# BSB-LAN-Full.net
KiCad netlist of a schematic drawn in EAGLE
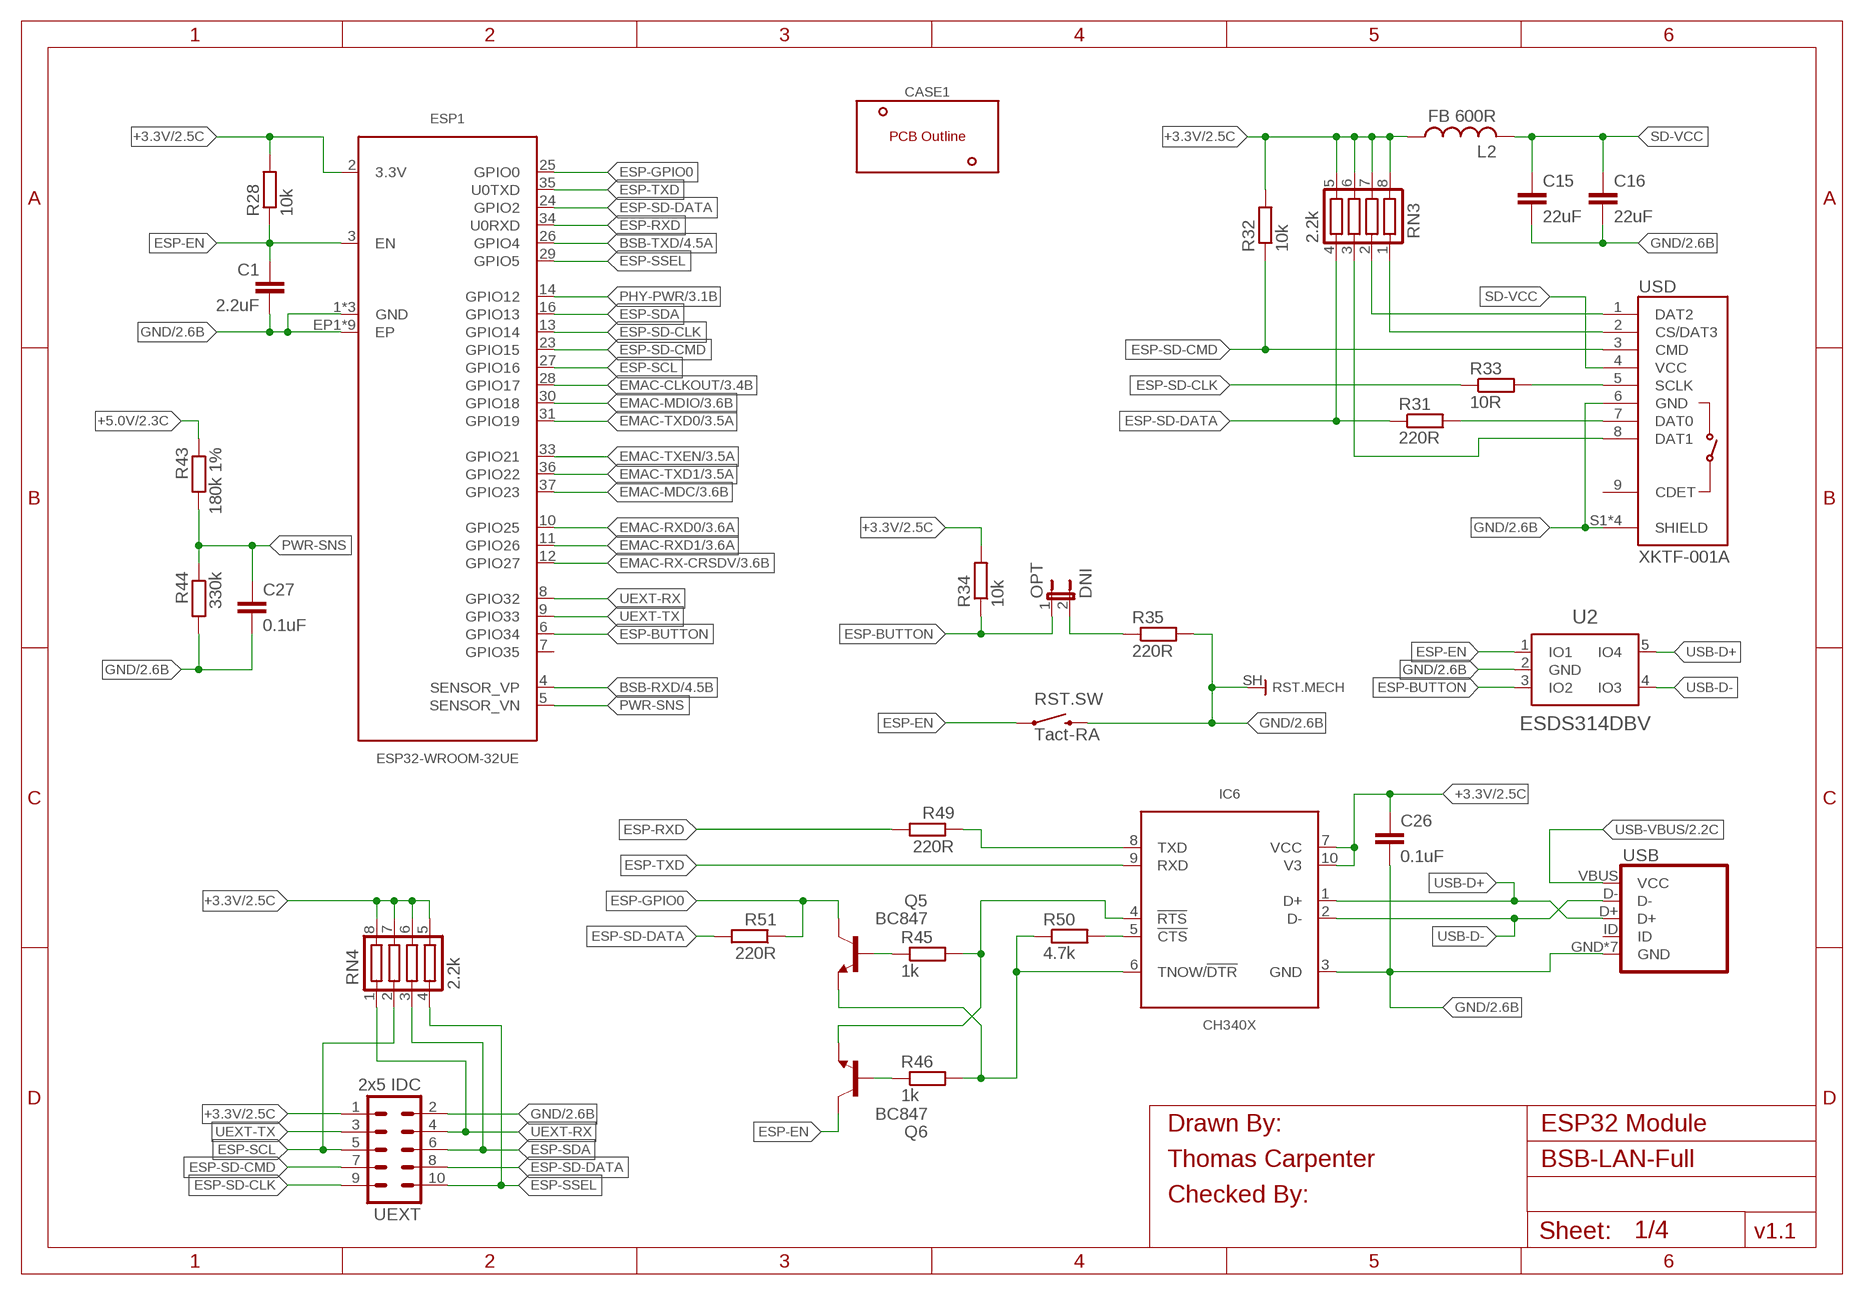
[diagram p0: schematic, sheet 1]
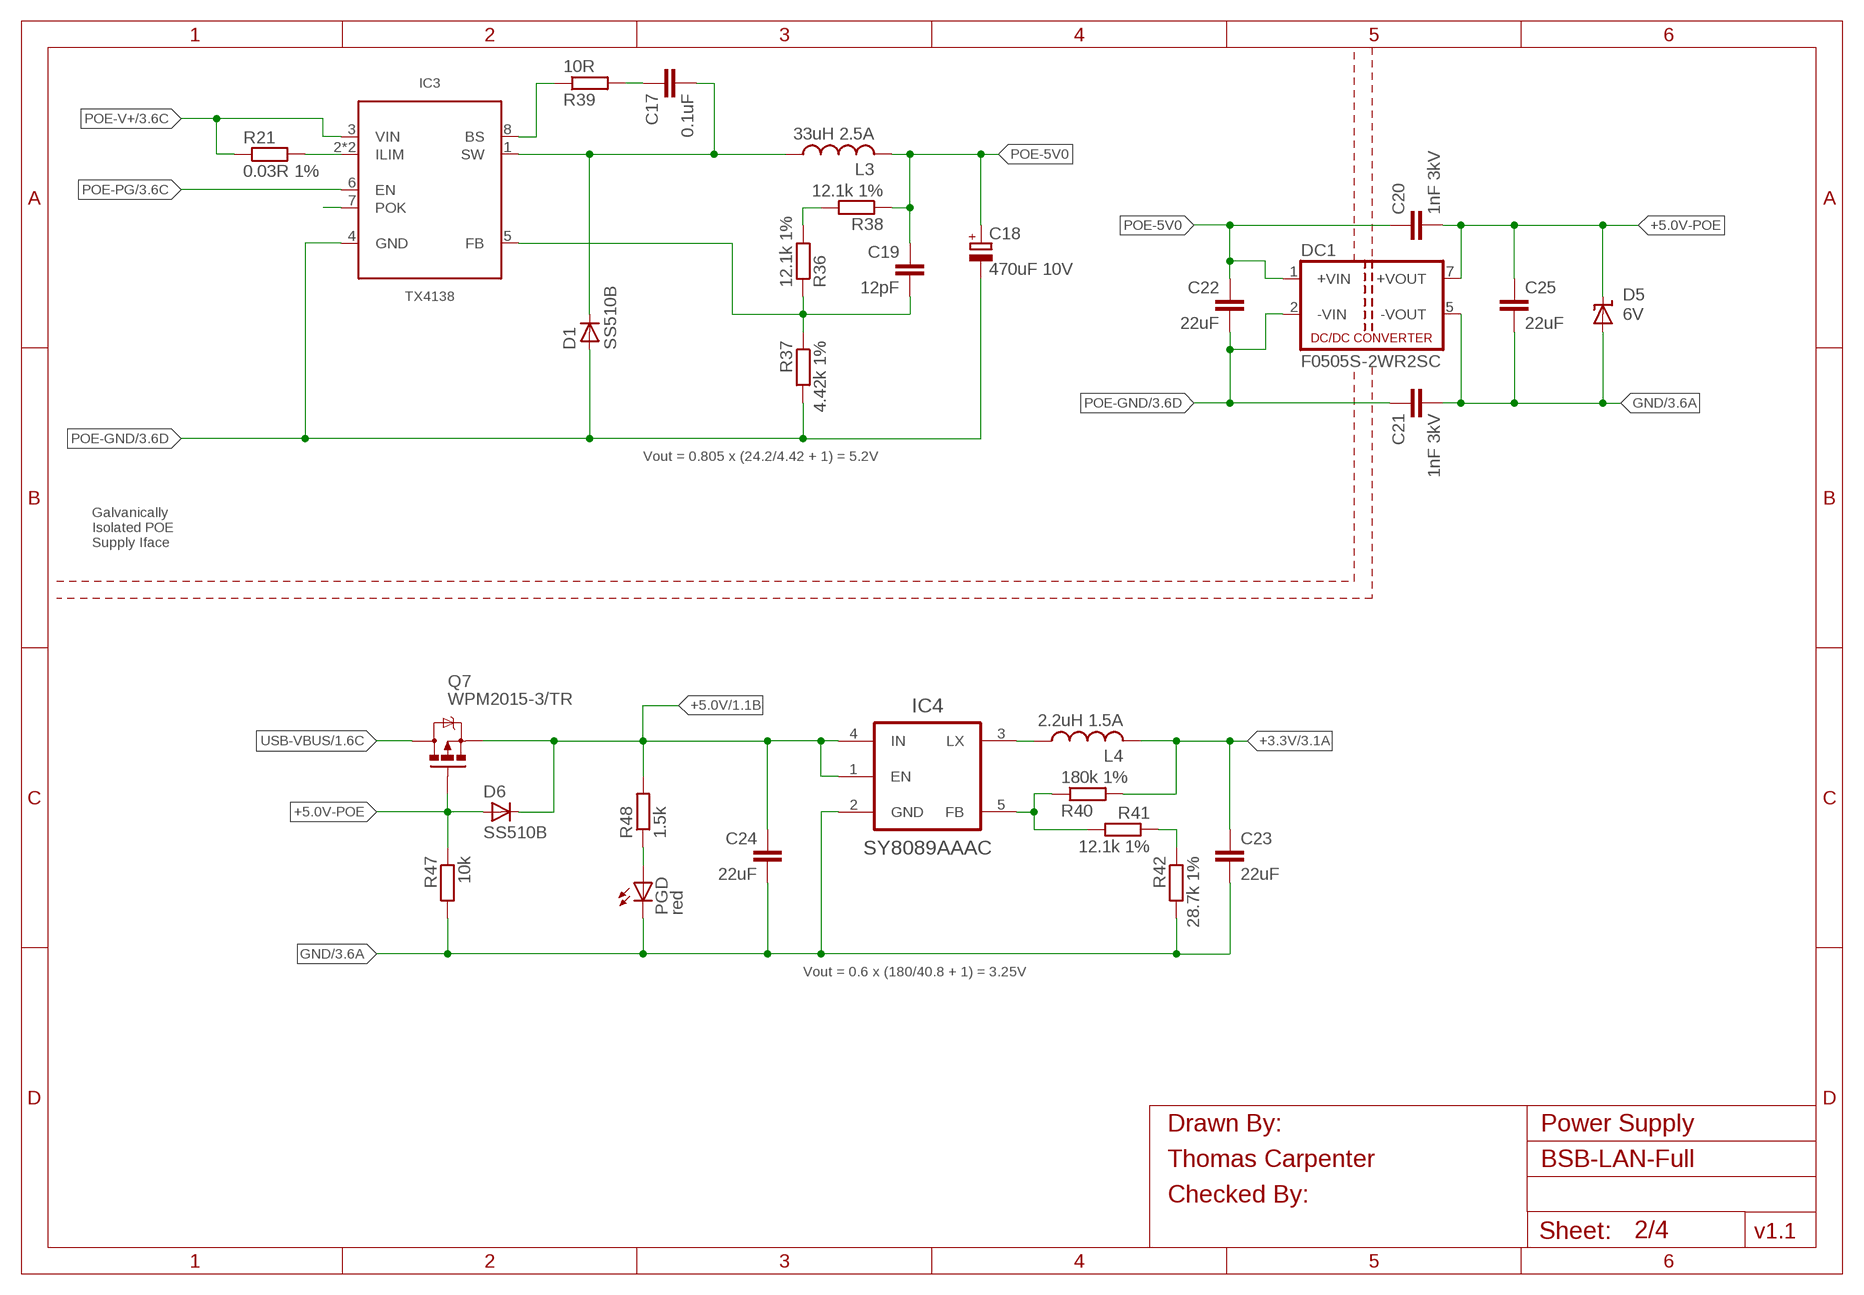
[diagram p1: schematic, sheet 2]
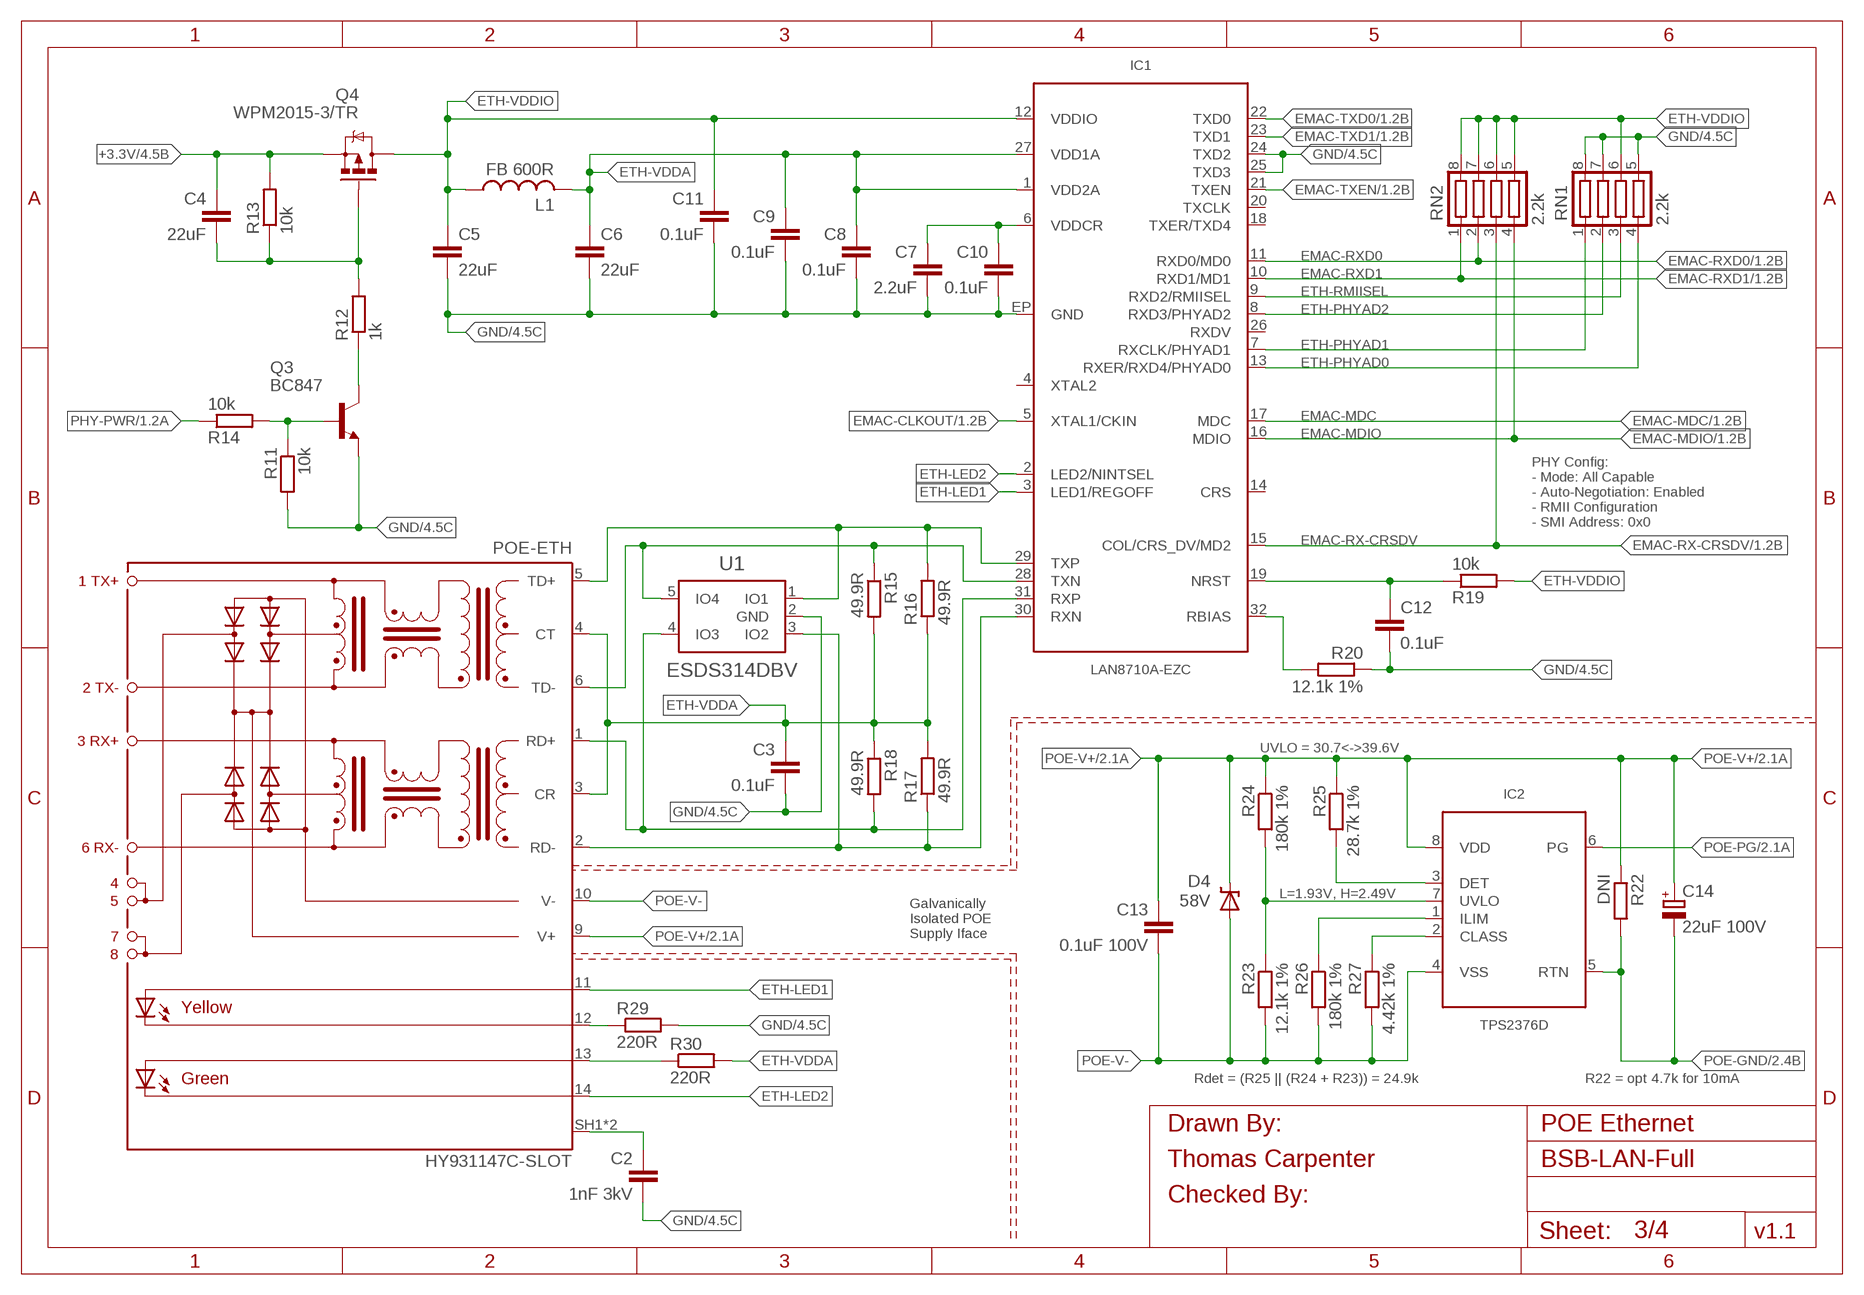
[diagram p2: schematic, sheet 3]
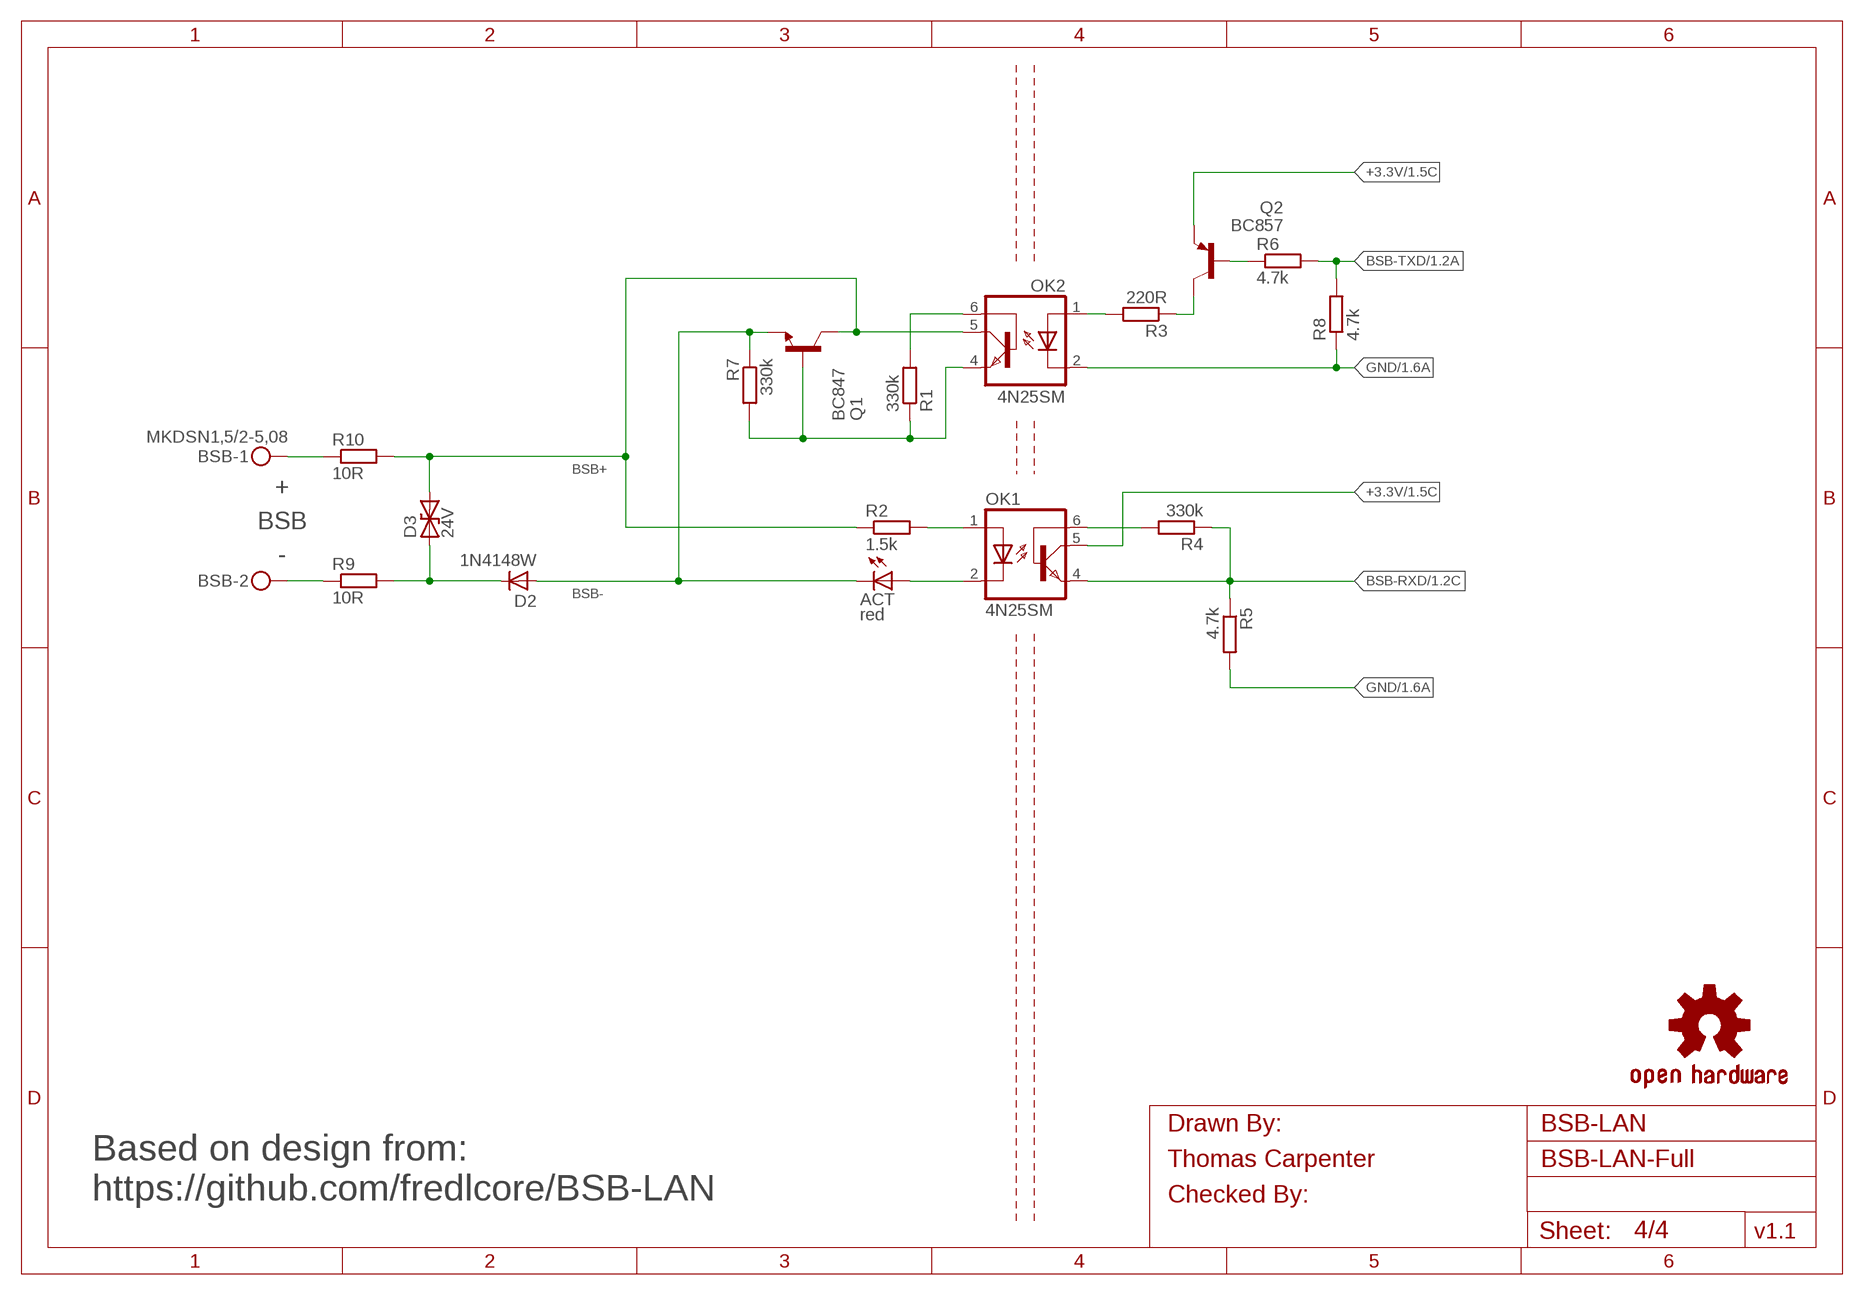
[diagram p3: schematic, sheet 4]

(export (version "E")
  (design (tool "Eeschema 10.0.6"))
  (components
    (comp (ref "ACT")
      (value "red")
      (footprint "eagle-import:CHIP-LED0603")
      (fields (field (name "LCSC_PART") "C2286"))
      (libsource (lib "eagle-import") (part "LEDCHIPLED_0603"))
    )
    (comp (ref "BSB")
      (value "MKDSN1,5/2-5,08")
      (footprint "eagle-import:MKDSN1_5-2-5_08")
      (fields (field (name "LCSC_PART") "C5183989"))
      (libsource (lib "eagle-import") (part "MKDSN1,5/2-5,08"))
    )
    (comp (ref "D2")
      (value "1N4148W")
      (footprint "eagle-import:SOD123")
      (fields (field (name "LCSC_PART") "C81598"))
      (libsource (lib "eagle-import") (part "DIODE-SOD123"))
    )
    (comp (ref "D3")
      (value "24V")
      (footprint "eagle-import:SMBG")
      (fields (field (name "LCSC_PART") "C83268"))
      (libsource (lib "eagle-import") (part "TVS-BIDIRSMB"))
    )
    (comp (ref "OK1")
      (value "4N25SM")
      (footprint "eagle-import:DIL6-SMD")
      (fields (field (name "LCSC_PART") "C258246") (field (name "LCSC_PART_1") "C258246"))
      (libsource (lib "eagle-import") (part "4N?MS25"))
    )
    (comp (ref "OK2")
      (value "4N25SM")
      (footprint "eagle-import:DIL6-SMD")
      (fields (field (name "LCSC_PART") "C258246") (field (name "LCSC_PART_1") "C258246"))
      (libsource (lib "eagle-import") (part "4N?MS25"))
    )
    (comp (ref "Q1")
      (value "BC847")
      (footprint "eagle-import:SOT23")
      (fields (field (name "LCSC_PART") "C130417") (field (name "LCSC_PART_1") "C130417"))
      (libsource (lib "eagle-import") (part "BC847"))
    )
    (comp (ref "Q2")
      (value "BC857")
      (footprint "eagle-import:SOT23-BEC")
      (fields (field (name "LCSC_PART") "C426782") (field (name "LCSC_PART_1") "C426782"))
      (libsource (lib "eagle-import") (part "BC857"))
    )
    (comp (ref "R1")
      (value "330k")
      (footprint "eagle-import:R0603")
      (fields (field (name "LCSC_PART") "C23137"))
      (libsource (lib "eagle-import") (part "R-EU_R0603"))
    )
    (comp (ref "R2")
      (value "1.5k")
      (footprint "eagle-import:R0603")
      (fields (field (name "LCSC_PART") "C22843"))
      (libsource (lib "eagle-import") (part "R-EU_R0603"))
    )
    (comp (ref "R3")
      (value "220R")
      (footprint "eagle-import:R0402")
      (fields (field (name "LCSC_PART") "C25091"))
      (libsource (lib "eagle-import") (part "R-EU_R0402"))
    )
    (comp (ref "R4")
      (value "330k")
      (footprint "eagle-import:R0603")
      (fields (field (name "LCSC_PART") "C23137"))
      (libsource (lib "eagle-import") (part "R-EU_R0603"))
    )
    (comp (ref "R5")
      (value "4.7k")
      (footprint "eagle-import:R0402")
      (fields (field (name "LCSC_PART") "C25900"))
      (libsource (lib "eagle-import") (part "R-EU_R0402"))
    )
    (comp (ref "R6")
      (value "4.7k")
      (footprint "eagle-import:R0402")
      (fields (field (name "LCSC_PART") "C25900"))
      (libsource (lib "eagle-import") (part "R-EU_R0402"))
    )
    (comp (ref "R7")
      (value "330k")
      (footprint "eagle-import:R0603")
      (fields (field (name "LCSC_PART") "C23137"))
      (libsource (lib "eagle-import") (part "R-EU_R0603"))
    )
    (comp (ref "R8")
      (value "4.7k")
      (footprint "eagle-import:R0402")
      (fields (field (name "LCSC_PART") "C25900"))
      (libsource (lib "eagle-import") (part "R-EU_R0402"))
    )
    (comp (ref "R9")
      (value "10R")
      (footprint "eagle-import:R0603")
      (fields (field (name "LCSC_PART") "C22859"))
      (libsource (lib "eagle-import") (part "R-EU_R0603"))
    )
    (comp (ref "R10")
      (value "10R")
      (footprint "eagle-import:R0603")
      (fields (field (name "LCSC_PART") "C22859"))
      (libsource (lib "eagle-import") (part "R-EU_R0603"))
    )
    (comp (ref "U$3")
      (value "DNI")
      (footprint "eagle-import:OSHW-LOGO-M")
      (libsource (lib "eagle-import") (part "OSHW-LOGOM"))
    )
    (comp (ref "C1")
      (value "2.2uF")
      (footprint "eagle-import:C0603")
      (fields (field (name "LCSC_PART") "C23630"))
      (libsource (lib "eagle-import") (part "C-EUC0603"))
    )
    (comp (ref "C15")
      (value "22uF")
      (footprint "eagle-import:C0805L")
      (fields (field (name "LCSC_PART") "C45783"))
      (libsource (lib "eagle-import") (part "C-EUC0805L"))
    )
    (comp (ref "C16")
      (value "22uF")
      (footprint "eagle-import:C0805L")
      (fields (field (name "LCSC_PART") "C45783"))
      (libsource (lib "eagle-import") (part "C-EUC0805L"))
    )
    (comp (ref "C26")
      (value "0.1uF")
      (footprint "eagle-import:C0603L")
      (fields (field (name "LCSC_PART") "C113803"))
      (libsource (lib "eagle-import") (part "C-EUC0603L"))
    )
    (comp (ref "C27")
      (value "0.1uF")
      (footprint "eagle-import:C0603L")
      (fields (field (name "LCSC_PART") "C113803"))
      (libsource (lib "eagle-import") (part "C-EUC0603L"))
    )
    (comp (ref "CASE1")
      (value "DNI")
      (footprint "eagle-import:CNMB_2-")
      (libsource (lib "eagle-import") (part "CNMB/2"))
    )
    (comp (ref "ESP1")
      (value "ESP32-WROOM-32UE")
      (footprint "eagle-import:ESP32-WROOM-32UE")
      (fields (field (name "LCSC_PART") "C701344"))
      (libsource (lib "eagle-import") (part "ESP32-WROOM-32UE"))
    )
    (comp (ref "IC6")
      (value "CH340X")
      (footprint "eagle-import:MSOP10")
      (fields (field (name "LCSC_PART") "C3035748"))
      (libsource (lib "eagle-import") (part "CH340X"))
    )
    (comp (ref "L2")
      (value "FB 600R")
      (footprint "eagle-import:L2010")
      (fields (field (name "LCSC_PART") "C1017"))
      (libsource (lib "eagle-import") (part "L-USL0805"))
    )
    (comp (ref "OPT")
      (value "DNI")
      (footprint "eagle-import:1X02-2MM")
      (libsource (lib "eagle-import") (part "JUMPER-2-2MM"))
    )
    (comp (ref "Q5")
      (value "BC847")
      (footprint "eagle-import:SOT23")
      (fields (field (name "LCSC_PART") "C130417") (field (name "LCSC_PART_1") "C130417"))
      (libsource (lib "eagle-import") (part "BC847"))
    )
    (comp (ref "Q6")
      (value "BC847")
      (footprint "eagle-import:SOT23")
      (fields (field (name "LCSC_PART") "C130417"))
      (libsource (lib "eagle-import") (part "BC847"))
    )
    (comp (ref "R28")
      (value "10k")
      (footprint "eagle-import:R0402")
      (fields (field (name "LCSC_PART") "C25744"))
      (libsource (lib "eagle-import") (part "R-EU_R0402"))
    )
    (comp (ref "R31")
      (value "220R")
      (footprint "eagle-import:R0402")
      (fields (field (name "LCSC_PART") "C25091"))
      (libsource (lib "eagle-import") (part "R-EU_R0402"))
    )
    (comp (ref "R32")
      (value "10k")
      (footprint "eagle-import:R0402")
      (fields (field (name "LCSC_PART") "C25744"))
      (libsource (lib "eagle-import") (part "R-EU_R0402"))
    )
    (comp (ref "R33")
      (value "10R")
      (footprint "eagle-import:R0603L")
      (fields (field (name "LCSC_PART") "C22859"))
      (libsource (lib "eagle-import") (part "R-EU_R0603L"))
    )
    (comp (ref "R34")
      (value "10k")
      (footprint "eagle-import:R0402")
      (fields (field (name "LCSC_PART") "C25744"))
      (libsource (lib "eagle-import") (part "R-EU_R0402"))
    )
    (comp (ref "R35")
      (value "220R")
      (footprint "eagle-import:R0402")
      (fields (field (name "LCSC_PART") "C25091"))
      (libsource (lib "eagle-import") (part "R-EU_R0402"))
    )
    (comp (ref "R43")
      (value "180k 1%")
      (footprint "eagle-import:R0402")
      (fields (field (name "LCSC_PART") "C25760"))
      (libsource (lib "eagle-import") (part "R-EU_R0402"))
    )
    (comp (ref "R44")
      (value "330k")
      (footprint "eagle-import:R0603L")
      (fields (field (name "LCSC_PART") "C23137"))
      (libsource (lib "eagle-import") (part "R-EU_R0603L"))
    )
    (comp (ref "R45")
      (value "1k")
      (footprint "eagle-import:R0402")
      (fields (field (name "LCSC_PART") "C11702"))
      (libsource (lib "eagle-import") (part "R-EU_R0402"))
    )
    (comp (ref "R46")
      (value "1k")
      (footprint "eagle-import:R0402")
      (fields (field (name "LCSC_PART") "C11702"))
      (libsource (lib "eagle-import") (part "R-EU_R0402"))
    )
    (comp (ref "R49")
      (value "220R")
      (footprint "eagle-import:R0402")
      (fields (field (name "LCSC_PART") "C25091"))
      (libsource (lib "eagle-import") (part "R-EU_R0402"))
    )
    (comp (ref "R50")
      (value "4.7k")
      (footprint "eagle-import:R0402")
      (fields (field (name "LCSC_PART") "C25900"))
      (libsource (lib "eagle-import") (part "R-EU_R0402"))
    )
    (comp (ref "R51")
      (value "220R")
      (footprint "eagle-import:R0402")
      (fields (field (name "LCSC_PART") "C25091"))
      (libsource (lib "eagle-import") (part "R-EU_R0402"))
    )
    (comp (ref "RN3")
      (value "2.2k")
      (footprint "eagle-import:CTS742C083")
      (fields (field (name "LCSC_PART") "C414564"))
      (libsource (lib "eagle-import") (part "R-NET-04-R1206"))
    )
    (comp (ref "RN4")
      (value "2.2k")
      (footprint "eagle-import:CTS742C083")
      (fields (field (name "LCSC_PART") "C414564"))
      (libsource (lib "eagle-import") (part "R-NET-04-R1206"))
    )
    (comp (ref "RST")
      (value "Tact-RA")
      (footprint "eagle-import:TACTILE_SWITCH_SMD_SIDE_SHL")
      (fields (field (name "LCSC_PART") "C495926"))
      (libsource (lib "eagle-import") (part "SWITCH-MOMENTARY-SHELL-SMD-RA"))
    )
    (comp (ref "U2")
      (value "ESDS314DBV")
      (footprint "eagle-import:DBV0005A-SOT23")
      (fields (field (name "LCSC_PART") "C1847859"))
      (libsource (lib "eagle-import") (part "ESDS314DBV"))
    )
    (comp (ref "UEXT")
      (value "2x5 IDC")
      (footprint "eagle-import:ML10")
      (fields (field (name "LCSC_PART") "C5665"))
      (libsource (lib "eagle-import") (part "ML10"))
    )
    (comp (ref "USB")
      (value "ZX62-B-5PA(33)")
      (footprint "eagle-import:USB-MICROB")
      (fields (field (name "LCSC_PART") "C132561"))
      (libsource (lib "eagle-import") (part "USB_MICROB_PLUG"))
    )
    (comp (ref "USD")
      (value "XKTF-001A")
      (footprint "eagle-import:MICRO-SD")
      (fields (field (name "LCSC_PART") "C381079"))
      (libsource (lib "eagle-import") (part "MICROSD"))
    )
    (comp (ref "C2")
      (value "1nF 3kV")
      (footprint "eagle-import:C1808")
      (fields (field (name "LCSC_PART") "C577300"))
      (libsource (lib "eagle-import") (part "C-EUC1808"))
    )
    (comp (ref "C3")
      (value "0.1uF")
      (footprint "eagle-import:C0603")
      (fields (field (name "LCSC_PART") "C113803"))
      (libsource (lib "eagle-import") (part "C-EUC0603"))
    )
    (comp (ref "C4")
      (value "22uF")
      (footprint "eagle-import:C0805L")
      (fields (field (name "LCSC_PART") "C45783"))
      (libsource (lib "eagle-import") (part "C-EUC0805L"))
    )
    (comp (ref "C5")
      (value "22uF")
      (footprint "eagle-import:C0805L")
      (fields (field (name "LCSC_PART") "C45783"))
      (libsource (lib "eagle-import") (part "C-EUC0805L"))
    )
    (comp (ref "C6")
      (value "22uF")
      (footprint "eagle-import:C0805L")
      (fields (field (name "LCSC_PART") "C45783"))
      (libsource (lib "eagle-import") (part "C-EUC0805L"))
    )
    (comp (ref "C7")
      (value "2.2uF")
      (footprint "eagle-import:C0603")
      (fields (field (name "LCSC_PART") "C23630"))
      (libsource (lib "eagle-import") (part "C-EUC0603"))
    )
    (comp (ref "C8")
      (value "0.1uF")
      (footprint "eagle-import:C0603L")
      (fields (field (name "LCSC_PART") "C113803"))
      (libsource (lib "eagle-import") (part "C-EUC0603L"))
    )
    (comp (ref "C9")
      (value "0.1uF")
      (footprint "eagle-import:C0603L")
      (fields (field (name "LCSC_PART") "C113803"))
      (libsource (lib "eagle-import") (part "C-EUC0603L"))
    )
    (comp (ref "C10")
      (value "0.1uF")
      (footprint "eagle-import:C0603L")
      (fields (field (name "LCSC_PART") "C113803"))
      (libsource (lib "eagle-import") (part "C-EUC0603L"))
    )
    (comp (ref "C11")
      (value "0.1uF")
      (footprint "eagle-import:C0603L")
      (fields (field (name "LCSC_PART") "C113803"))
      (libsource (lib "eagle-import") (part "C-EUC0603L"))
    )
    (comp (ref "C12")
      (value "0.1uF")
      (footprint "eagle-import:C0603L")
      (fields (field (name "LCSC_PART") "C113803"))
      (libsource (lib "eagle-import") (part "C-EUC0603L"))
    )
    (comp (ref "C13")
      (value "0.1uF 100V")
      (footprint "eagle-import:C0603")
      (fields (field (name "LCSC_PART") "C113803"))
      (libsource (lib "eagle-import") (part "C-EUC0603"))
    )
    (comp (ref "C14")
      (value "22uF 100V")
      (footprint "eagle-import:PANASONIC_D")
      (fields (field (name "LCSC_PART") "C487431"))
      (libsource (lib "eagle-import") (part "CPOL-EUD"))
    )
    (comp (ref "D4")
      (value "58V")
      (footprint "eagle-import:SMA")
      (fields (field (name "LCSC_PART") "C151246"))
      (libsource (lib "eagle-import") (part "TVS-UNISMA"))
    )
    (comp (ref "IC1")
      (value "LAN8710A-EZC")
      (footprint "eagle-import:QFN-5X5-32")
      (fields (field (name "LCSC_PART") "C46185"))
      (libsource (lib "eagle-import") (part "LAN8710A-EZC"))
    )
    (comp (ref "IC2")
      (value "TPS2376D")
      (footprint "eagle-import:SOIC8")
      (fields (field (name "LCSC_PART") "C2859892"))
      (libsource (lib "eagle-import") (part "TPS237D6"))
    )
    (comp (ref "L1")
      (value "FB 600R")
      (footprint "eagle-import:L2010")
      (fields (field (name "LCSC_PART") "C1017"))
      (libsource (lib "eagle-import") (part "L-USL0805"))
    )
    (comp (ref "POE-ETH")
      (value "HY931147C-SLOT")
      (footprint "eagle-import:HY931147C-SLOT")
      (fields (field (name "LCSC_PART") "C91754"))
      (libsource (lib "eagle-import") (part "HY931147C-SLOT"))
    )
    (comp (ref "Q3")
      (value "BC847")
      (footprint "eagle-import:SOT23")
      (fields (field (name "LCSC_PART") "C130417"))
      (libsource (lib "eagle-import") (part "BC847"))
    )
    (comp (ref "Q4")
      (value "WPM2015-3/TR")
      (footprint "eagle-import:SOT23")
      (fields (field (name "LCSC_PART") "C7472861"))
      (libsource (lib "eagle-import") (part "WPM2015-3/TR"))
    )
    (comp (ref "R11")
      (value "10k")
      (footprint "eagle-import:R0402")
      (fields (field (name "LCSC_PART") "C25744"))
      (libsource (lib "eagle-import") (part "R-EU_R0402"))
    )
    (comp (ref "R12")
      (value "1k")
      (footprint "eagle-import:R0402")
      (fields (field (name "LCSC_PART") "C11702"))
      (libsource (lib "eagle-import") (part "R-EU_R0402"))
    )
    (comp (ref "R13")
      (value "10k")
      (footprint "eagle-import:R0402")
      (fields (field (name "LCSC_PART") "C25744"))
      (libsource (lib "eagle-import") (part "R-EU_R0402"))
    )
    (comp (ref "R14")
      (value "10k")
      (footprint "eagle-import:R0402")
      (fields (field (name "LCSC_PART") "C25744"))
      (libsource (lib "eagle-import") (part "R-EU_R0402"))
    )
    (comp (ref "R15")
      (value "49.9R")
      (footprint "eagle-import:R0402L")
      (fields (field (name "LCSC_PART") "C25120"))
      (libsource (lib "eagle-import") (part "R-EU_R0402L"))
    )
    (comp (ref "R16")
      (value "49.9R")
      (footprint "eagle-import:R0402L")
      (fields (field (name "LCSC_PART") "C25120"))
      (libsource (lib "eagle-import") (part "R-EU_R0402L"))
    )
    (comp (ref "R17")
      (value "49.9R")
      (footprint "eagle-import:R0402L")
      (fields (field (name "LCSC_PART") "C25120"))
      (libsource (lib "eagle-import") (part "R-EU_R0402L"))
    )
    (comp (ref "R18")
      (value "49.9R")
      (footprint "eagle-import:R0402L")
      (fields (field (name "LCSC_PART") "C25120"))
      (libsource (lib "eagle-import") (part "R-EU_R0402L"))
    )
    (comp (ref "R19")
      (value "10k")
      (footprint "eagle-import:R0402")
      (fields (field (name "LCSC_PART") "C25744"))
      (libsource (lib "eagle-import") (part "R-EU_R0402"))
    )
    (comp (ref "R20")
      (value "12.1k 1%")
      (footprint "eagle-import:R0402")
      (fields (field (name "LCSC_PART") "C25852"))
      (libsource (lib "eagle-import") (part "R-EU_R0402"))
    )
    (comp (ref "R22")
      (value "DNI")
      (footprint "eagle-import:R1206")
      (libsource (lib "eagle-import") (part "R-EU_R1206"))
    )
    (comp (ref "R23")
      (value "12.1k 1%")
      (footprint "eagle-import:R0402")
      (fields (field (name "LCSC_PART") "C25852"))
      (libsource (lib "eagle-import") (part "R-EU_R0402"))
    )
    (comp (ref "R24")
      (value "180k 1%")
      (footprint "eagle-import:R0402")
      (fields (field (name "LCSC_PART") "C25760"))
      (libsource (lib "eagle-import") (part "R-EU_R0402"))
    )
    (comp (ref "R25")
      (value "28.7k 1%")
      (footprint "eagle-import:R0402")
      (fields (field (name "LCSC_PART") "C26972"))
      (libsource (lib "eagle-import") (part "R-EU_R0402"))
    )
    (comp (ref "R26")
      (value "180k 1%")
      (footprint "eagle-import:R0402")
      (fields (field (name "LCSC_PART") "C25760"))
      (libsource (lib "eagle-import") (part "R-EU_R0402"))
    )
    (comp (ref "R27")
      (value "4.42k 1%")
      (footprint "eagle-import:R0402")
      (fields (field (name "LCSC_PART") "C52269"))
      (libsource (lib "eagle-import") (part "R-EU_R0402"))
    )
    (comp (ref "R29")
      (value "220R")
      (footprint "eagle-import:R0402")
      (fields (field (name "LCSC_PART") "C25091"))
      (libsource (lib "eagle-import") (part "R-EU_R0402"))
    )
    (comp (ref "R30")
      (value "220R")
      (footprint "eagle-import:R0402")
      (fields (field (name "LCSC_PART") "C25091"))
      (libsource (lib "eagle-import") (part "R-EU_R0402"))
    )
    (comp (ref "RN1")
      (value "2.2k")
      (footprint "eagle-import:CTS742C083")
      (fields (field (name "LCSC_PART") "C414564"))
      (libsource (lib "eagle-import") (part "R-NET-04-R1206"))
    )
    (comp (ref "RN2")
      (value "2.2k")
      (footprint "eagle-import:CTS742C083")
      (fields (field (name "LCSC_PART") "C414564"))
      (libsource (lib "eagle-import") (part "R-NET-04-R1206"))
    )
    (comp (ref "U1")
      (value "ESDS314DBV")
      (footprint "eagle-import:DBV0005A-SOT23")
      (fields (field (name "LCSC_PART") "C1847859"))
      (libsource (lib "eagle-import") (part "ESDS314DBV"))
    )
    (comp (ref "C17")
      (value "0.1uF")
      (footprint "eagle-import:C0603L")
      (fields (field (name "LCSC_PART") "C113803"))
      (libsource (lib "eagle-import") (part "C-EUC0603L"))
    )
    (comp (ref "C18")
      (value "470uF 10V")
      (footprint "eagle-import:SMC_D")
      (fields (field (name "LCSC_PART") "C4944894"))
      (libsource (lib "eagle-import") (part "CPOL-EUSMCD"))
    )
    (comp (ref "C19")
      (value "12pF")
      (footprint "eagle-import:C0402")
      (fields (field (name "LCSC_PART") "C1547"))
      (libsource (lib "eagle-import") (part "C-EUC0402"))
    )
    (comp (ref "C20")
      (value "1nF 3kV")
      (footprint "eagle-import:C1808")
      (fields (field (name "LCSC_PART") "C577300"))
      (libsource (lib "eagle-import") (part "C-EUC1808"))
    )
    (comp (ref "C21")
      (value "1nF 3kV")
      (footprint "eagle-import:C1808")
      (fields (field (name "LCSC_PART") "C577300"))
      (libsource (lib "eagle-import") (part "C-EUC1808"))
    )
    (comp (ref "C22")
      (value "22uF")
      (footprint "eagle-import:C0805")
      (fields (field (name "LCSC_PART") "C45783"))
      (libsource (lib "eagle-import") (part "C-EUC0805"))
    )
    (comp (ref "C23")
      (value "22uF")
      (footprint "eagle-import:C0805")
      (fields (field (name "LCSC_PART") "C45783"))
      (libsource (lib "eagle-import") (part "C-EUC0805"))
    )
    (comp (ref "C24")
      (value "22uF")
      (footprint "eagle-import:C0805")
      (fields (field (name "LCSC_PART") "C45783"))
      (libsource (lib "eagle-import") (part "C-EUC0805"))
    )
    (comp (ref "C25")
      (value "22uF")
      (footprint "eagle-import:C0805")
      (fields (field (name "LCSC_PART") "C45783"))
      (libsource (lib "eagle-import") (part "C-EUC0805"))
    )
    (comp (ref "D1")
      (value "SS510B")
      (footprint "eagle-import:SMB")
      (fields (field (name "LCSC_PART") "C65011"))
      (libsource (lib "eagle-import") (part "DIODE-SMB"))
    )
    (comp (ref "D5")
      (value "6V")
      (footprint "eagle-import:SMA")
      (fields (field (name "LCSC_PART") "C223993"))
      (libsource (lib "eagle-import") (part "TVS-UNISMA"))
    )
    (comp (ref "D6")
      (value "SS510B")
      (footprint "eagle-import:SMB")
      (fields (field (name "LCSC_PART") "C65011"))
      (libsource (lib "eagle-import") (part "DIODE-SMB"))
    )
    (comp (ref "DC1")
      (value "F0505S-2WR2SC")
      (footprint "eagle-import:SIP7-N")
      (fields (field (name "LCSC_PART") "C909777"))
      (libsource (lib "eagle-import") (part "FS-2WR2SC0505"))
    )
    (comp (ref "IC3")
      (value "TX4138")
      (footprint "eagle-import:SOIC8-EP")
      (fields (field (name "LCSC_PART") "C329267"))
      (libsource (lib "eagle-import") (part "TX4138"))
    )
    (comp (ref "IC4")
      (value "SY8089AAAC")
      (footprint "eagle-import:DBV0005A-SOT23")
      (fields (field (name "LCSC_PART") "C78988"))
      (libsource (lib "eagle-import") (part "SY8089?CAAA"))
    )
    (comp (ref "L3")
      (value "33uH 2.5A")
      (footprint "eagle-import:L6560P")
      (fields (field (name "LCSC_PART") "C2839927"))
      (libsource (lib "eagle-import") (part "L-USL6560P"))
    )
    (comp (ref "L4")
      (value "2.2uH 1.5A")
      (footprint "eagle-import:L4040P")
      (fields (field (name "LCSC_PART") "C135262"))
      (libsource (lib "eagle-import") (part "L-USL4040P"))
    )
    (comp (ref "PGD")
      (value "red")
      (footprint "eagle-import:CHIP-LED0603")
      (fields (field (name "LCSC_PART") "C2286"))
      (libsource (lib "eagle-import") (part "LEDCHIPLED_0603"))
    )
    (comp (ref "Q7")
      (value "WPM2015-3/TR")
      (footprint "eagle-import:SOT23")
      (fields (field (name "LCSC_PART") "C7472861"))
      (libsource (lib "eagle-import") (part "WPM2015-3/TR"))
    )
    (comp (ref "R21")
      (value "0.03R 1%")
      (footprint "eagle-import:R1206")
      (fields (field (name "LCSC_PART") "C163046"))
      (libsource (lib "eagle-import") (part "R-EU_R1206"))
    )
    (comp (ref "R36")
      (value "12.1k 1%")
      (footprint "eagle-import:R0402")
      (fields (field (name "LCSC_PART") "C25852"))
      (libsource (lib "eagle-import") (part "R-EU_R0402"))
    )
    (comp (ref "R37")
      (value "4.42k 1%")
      (footprint "eagle-import:R0402")
      (fields (field (name "LCSC_PART") "C52269"))
      (libsource (lib "eagle-import") (part "R-EU_R0402"))
    )
    (comp (ref "R38")
      (value "12.1k 1%")
      (footprint "eagle-import:R0402")
      (fields (field (name "LCSC_PART") "C25852"))
      (libsource (lib "eagle-import") (part "R-EU_R0402"))
    )
    (comp (ref "R39")
      (value "10R")
      (footprint "eagle-import:R0603L")
      (fields (field (name "LCSC_PART") "C22859"))
      (libsource (lib "eagle-import") (part "R-EU_R0603L"))
    )
    (comp (ref "R40")
      (value "180k 1%")
      (footprint "eagle-import:R0402")
      (fields (field (name "LCSC_PART") "C25760"))
      (libsource (lib "eagle-import") (part "R-EU_R0402"))
    )
    (comp (ref "R41")
      (value "12.1k 1%")
      (footprint "eagle-import:R0402")
      (fields (field (name "LCSC_PART") "C25852"))
      (libsource (lib "eagle-import") (part "R-EU_R0402"))
    )
    (comp (ref "R42")
      (value "28.7k 1%")
      (footprint "eagle-import:R0402")
      (fields (field (name "LCSC_PART") "C26972"))
      (libsource (lib "eagle-import") (part "R-EU_R0402"))
    )
    (comp (ref "R47")
      (value "10k")
      (footprint "eagle-import:R0402")
      (fields (field (name "LCSC_PART") "C25744"))
      (libsource (lib "eagle-import") (part "R-EU_R0402"))
    )
    (comp (ref "R48")
      (value "1.5k")
      (footprint "eagle-import:R0603")
      (fields (field (name "LCSC_PART") "C22843"))
      (libsource (lib "eagle-import") (part "R-EU_R0603"))
    )
  )
  (nets
    (net (code "1") (name "+3.3V") (class "Default")
      (node (ref "C23") (pin "1") (pinfunction "1_1") (pintype "passive"))
      (node (ref "C26") (pin "1") (pinfunction "1_1") (pintype "passive"))
      (node (ref "C4") (pin "1") (pinfunction "1_1") (pintype "passive"))
      (node (ref "ESP1") (pin "2") (pinfunction "3.3V_2") (pintype "power_in"))
      (node (ref "IC6") (pin "10") (pinfunction "V3_10") (pintype "power_in"))
      (node (ref "IC6") (pin "7") (pinfunction "VCC_7") (pintype "power_in"))
      (node (ref "L2") (pin "1") (pinfunction "1_1") (pintype "passive"))
      (node (ref "L4") (pin "2") (pinfunction "2_2") (pintype "passive"))
      (node (ref "OK1") (pin "5") (pinfunction "COL_5") (pintype "passive"))
      (node (ref "Q2") (pin "E") (pinfunction "E_E") (pintype "passive"))
      (node (ref "Q4") (pin "2") (pinfunction "S_2") (pintype "passive"))
      (node (ref "R13") (pin "2") (pinfunction "2_2") (pintype "passive"))
      (node (ref "R28") (pin "2") (pinfunction "2_2") (pintype "passive"))
      (node (ref "R32") (pin "2") (pinfunction "2_2") (pintype "passive"))
      (node (ref "R34") (pin "2") (pinfunction "2_2") (pintype "passive"))
      (node (ref "R40") (pin "2") (pinfunction "2_2") (pintype "passive"))
      (node (ref "RN3") (pin "5") (pinfunction "5_5") (pintype "passive"))
      (node (ref "RN3") (pin "6") (pinfunction "6_6") (pintype "passive"))
      (node (ref "RN3") (pin "7") (pinfunction "7_7") (pintype "passive"))
      (node (ref "RN3") (pin "8") (pinfunction "8_8") (pintype "passive"))
      (node (ref "RN4") (pin "5") (pinfunction "5_5") (pintype "passive"))
      (node (ref "RN4") (pin "6") (pinfunction "6_6") (pintype "passive"))
      (node (ref "RN4") (pin "7") (pinfunction "7_7") (pintype "passive"))
      (node (ref "RN4") (pin "8") (pinfunction "8_8") (pintype "passive"))
      (node (ref "UEXT") (pin "1") (pinfunction "1_1") (pintype "passive"))
    )
    (net (code "2") (name "+5.0V") (class "Default")
      (node (ref "C24") (pin "1") (pinfunction "1_1") (pintype "passive"))
      (node (ref "D6") (pin "C") (pinfunction "C_C") (pintype "passive"))
      (node (ref "IC4") (pin "1") (pinfunction "EN_1") (pintype "input"))
      (node (ref "IC4") (pin "4") (pinfunction "IN_4") (pintype "power_in"))
      (node (ref "Q7") (pin "2") (pinfunction "S_2") (pintype "passive"))
      (node (ref "R43") (pin "1") (pinfunction "1_1") (pintype "passive"))
      (node (ref "R48") (pin "2") (pinfunction "2_2") (pintype "passive"))
    )
    (net (code "3") (name "+5.0V-POE") (class "Default")
      (node (ref "C20") (pin "2") (pinfunction "2_2") (pintype "passive"))
      (node (ref "C25") (pin "1") (pinfunction "1_1") (pintype "passive"))
      (node (ref "D5") (pin "C") (pinfunction "C_C") (pintype "passive"))
      (node (ref "D6") (pin "A") (pinfunction "A_A") (pintype "passive"))
      (node (ref "DC1") (pin "7") (pinfunction "+VOUT_7") (pintype "passive"))
      (node (ref "Q7") (pin "1") (pinfunction "G_1") (pintype "passive"))
      (node (ref "R47") (pin "1") (pinfunction "1_1") (pintype "passive"))
    )
    (net (code "4") (name "BSB+") (class "Default")
      (node (ref "D3") (pin "2") (pinfunction "2_2") (pintype "passive"))
      (node (ref "OK2") (pin "5") (pinfunction "COL_5") (pintype "passive"))
      (node (ref "Q1") (pin "3") (pinfunction "C_3") (pintype "passive"))
      (node (ref "R10") (pin "2") (pinfunction "2_2") (pintype "passive"))
      (node (ref "R2") (pin "1") (pinfunction "1_1") (pintype "passive"))
    )
    (net (code "5") (name "BSB-") (class "Default")
      (node (ref "ACT") (pin "C") (pinfunction "C_C") (pintype "passive"))
      (node (ref "D2") (pin "A") (pinfunction "A_A") (pintype "passive"))
      (node (ref "Q1") (pin "2") (pinfunction "E_2") (pintype "passive"))
      (node (ref "R7") (pin "1") (pinfunction "1_1") (pintype "passive"))
    )
    (net (code "6") (name "BSB-RXD") (class "Default")
      (node (ref "ESP1") (pin "4") (pinfunction "SENSOR_VP_4") (pintype "bidirectional"))
      (node (ref "OK1") (pin "4") (pinfunction "EMI_4") (pintype "passive"))
      (node (ref "R4") (pin "1") (pinfunction "1_1") (pintype "passive"))
      (node (ref "R5") (pin "1") (pinfunction "1_1") (pintype "passive"))
    )
    (net (code "7") (name "BSB-TXD") (class "Default")
      (node (ref "ESP1") (pin "26") (pinfunction "GPIO4_26") (pintype "bidirectional"))
      (node (ref "R6") (pin "2") (pinfunction "2_2") (pintype "passive"))
      (node (ref "R8") (pin "2") (pinfunction "2_2") (pintype "passive"))
    )
    (net (code "8") (name "EMAC-CLKOUT") (class "Default")
      (node (ref "ESP1") (pin "28") (pinfunction "GPIO17_28") (pintype "bidirectional"))
      (node (ref "IC1") (pin "5") (pinfunction "XTAL1/CKIN_5") (pintype "input"))
    )
    (net (code "9") (name "EMAC-MDC") (class "Default")
      (node (ref "ESP1") (pin "37") (pinfunction "GPIO23_37") (pintype "bidirectional"))
      (node (ref "IC1") (pin "17") (pinfunction "MDC_17") (pintype "input"))
    )
    (net (code "10") (name "EMAC-MDIO") (class "Default")
      (node (ref "ESP1") (pin "30") (pinfunction "GPIO18_30") (pintype "bidirectional"))
      (node (ref "IC1") (pin "16") (pinfunction "MDIO_16") (pintype "bidirectional"))
      (node (ref "RN2") (pin "4") (pinfunction "4_4") (pintype "passive"))
    )
    (net (code "11") (name "EMAC-RX-CRSDV") (class "Default")
      (node (ref "ESP1") (pin "12") (pinfunction "GPIO27_12") (pintype "bidirectional"))
      (node (ref "IC1") (pin "15") (pinfunction "COL/CRS_DV/MD2_15") (pintype "bidirectional"))
      (node (ref "RN2") (pin "3") (pinfunction "3_3") (pintype "passive"))
    )
    (net (code "12") (name "EMAC-RXD0") (class "Default")
      (node (ref "ESP1") (pin "10") (pinfunction "GPIO25_10") (pintype "bidirectional"))
      (node (ref "IC1") (pin "11") (pinfunction "RXD0/MD0_11") (pintype "bidirectional"))
      (node (ref "RN2") (pin "2") (pinfunction "2_2") (pintype "passive"))
    )
    (net (code "13") (name "EMAC-RXD1") (class "Default")
      (node (ref "ESP1") (pin "11") (pinfunction "GPIO26_11") (pintype "bidirectional"))
      (node (ref "IC1") (pin "10") (pinfunction "RXD1/MD1_10") (pintype "bidirectional"))
      (node (ref "RN2") (pin "1") (pinfunction "1_1") (pintype "passive"))
    )
    (net (code "14") (name "EMAC-TXD0") (class "Default")
      (node (ref "ESP1") (pin "31") (pinfunction "GPIO19_31") (pintype "bidirectional"))
      (node (ref "IC1") (pin "22") (pinfunction "TXD0_22") (pintype "input"))
    )
    (net (code "15") (name "EMAC-TXD1") (class "Default")
      (node (ref "ESP1") (pin "36") (pinfunction "GPIO22_36") (pintype "bidirectional"))
      (node (ref "IC1") (pin "23") (pinfunction "TXD1_23") (pintype "input"))
    )
    (net (code "16") (name "EMAC-TXEN") (class "Default")
      (node (ref "ESP1") (pin "33") (pinfunction "GPIO21_33") (pintype "bidirectional"))
      (node (ref "IC1") (pin "21") (pinfunction "TXEN_21") (pintype "input"))
    )
    (net (code "17") (name "ESP-BUTTON") (class "Default")
      (node (ref "ESP1") (pin "6") (pinfunction "GPIO34_6") (pintype "bidirectional"))
      (node (ref "OPT") (pin "1") (pinfunction "1_1") (pintype "passive"))
      (node (ref "R34") (pin "1") (pinfunction "1_1") (pintype "passive"))
      (node (ref "U2") (pin "3") (pinfunction "IO2_3") (pintype "passive"))
    )
    (net (code "18") (name "ESP-EN") (class "Default")
      (node (ref "C1") (pin "1") (pinfunction "1_1") (pintype "passive"))
      (node (ref "ESP1") (pin "3") (pinfunction "EN_3") (pintype "input"))
      (node (ref "Q6") (pin "3") (pinfunction "C_3") (pintype "passive"))
      (node (ref "R28") (pin "1") (pinfunction "1_1") (pintype "passive"))
      (node (ref "RST") (pin "1") (pinfunction "1_1") (pintype "passive"))
      (node (ref "RST") (pin "2") (pinfunction "1_2") (pintype "passive"))
      (node (ref "U2") (pin "1") (pinfunction "IO1_1") (pintype "passive"))
    )
    (net (code "19") (name "ESP-GPIO0") (class "Default")
      (node (ref "ESP1") (pin "25") (pinfunction "GPIO0_25") (pintype "bidirectional"))
      (node (ref "Q5") (pin "3") (pinfunction "C_3") (pintype "passive"))
      (node (ref "R51") (pin "1") (pinfunction "1_1") (pintype "passive"))
    )
    (net (code "20") (name "ESP-RXD") (class "Default")
      (node (ref "ESP1") (pin "34") (pinfunction "U0RXD_34") (pintype "bidirectional"))
      (node (ref "R49") (pin "2") (pinfunction "2_2") (pintype "passive"))
    )
    (net (code "21") (name "ESP-SCL") (class "Default")
      (node (ref "ESP1") (pin "27") (pinfunction "GPIO16_27") (pintype "bidirectional"))
      (node (ref "RN4") (pin "2") (pinfunction "2_2") (pintype "passive"))
      (node (ref "UEXT") (pin "5") (pinfunction "5_5") (pintype "passive"))
    )
    (net (code "22") (name "ESP-SD-CLK") (class "Default")
      (node (ref "ESP1") (pin "13") (pinfunction "GPIO14_13") (pintype "bidirectional"))
      (node (ref "R33") (pin "1") (pinfunction "1_1") (pintype "passive"))
      (node (ref "UEXT") (pin "9") (pinfunction "9_9") (pintype "passive"))
    )
    (net (code "23") (name "ESP-SD-CMD") (class "Default")
      (node (ref "ESP1") (pin "23") (pinfunction "GPIO15_23") (pintype "bidirectional"))
      (node (ref "R32") (pin "1") (pinfunction "1_1") (pintype "passive"))
      (node (ref "UEXT") (pin "7") (pinfunction "7_7") (pintype "passive"))
      (node (ref "USD") (pin "3") (pinfunction "CMD_3") (pintype "bidirectional"))
    )
    (net (code "24") (name "ESP-SD-DATA") (class "Default")
      (node (ref "ESP1") (pin "24") (pinfunction "GPIO2_24") (pintype "bidirectional"))
      (node (ref "R31") (pin "1") (pinfunction "1_1") (pintype "passive"))
      (node (ref "R51") (pin "2") (pinfunction "2_2") (pintype "passive"))
      (node (ref "RN3") (pin "4") (pinfunction "4_4") (pintype "passive"))
      (node (ref "UEXT") (pin "8") (pinfunction "8_8") (pintype "passive"))
    )
    (net (code "25") (name "ESP-SDA") (class "Default")
      (node (ref "ESP1") (pin "16") (pinfunction "GPIO13_16") (pintype "bidirectional"))
      (node (ref "RN4") (pin "3") (pinfunction "3_3") (pintype "passive"))
      (node (ref "UEXT") (pin "6") (pinfunction "6_6") (pintype "passive"))
    )
    (net (code "26") (name "ESP-SSEL") (class "Default")
      (node (ref "ESP1") (pin "29") (pinfunction "GPIO5_29") (pintype "bidirectional"))
      (node (ref "RN4") (pin "4") (pinfunction "4_4") (pintype "passive"))
      (node (ref "UEXT") (pin "10") (pinfunction "10_10") (pintype "passive"))
    )
    (net (code "27") (name "ESP-TXD") (class "Default")
      (node (ref "ESP1") (pin "35") (pinfunction "U0TXD_35") (pintype "bidirectional"))
      (node (ref "IC6") (pin "9") (pinfunction "RXD_9") (pintype "input"))
    )
    (net (code "28") (name "ETH-LED1") (class "Default")
      (node (ref "IC1") (pin "3") (pinfunction "LED1/REGOFF_3") (pintype "bidirectional"))
      (node (ref "POE-ETH") (pin "11") (pinfunction "YA_11") (pintype "passive"))
    )
    (net (code "29") (name "ETH-LED2") (class "Default")
      (node (ref "IC1") (pin "2") (pinfunction "LED2/NINTSEL_2") (pintype "bidirectional"))
      (node (ref "POE-ETH") (pin "14") (pinfunction "GK_14") (pintype "passive"))
    )
    (net (code "30") (name "ETH-PHYAD0") (class "Default")
      (node (ref "IC1") (pin "13") (pinfunction "RXER/RXD4/PHYAD0_13") (pintype "bidirectional"))
      (node (ref "RN1") (pin "4") (pinfunction "4_4") (pintype "passive"))
    )
    (net (code "31") (name "ETH-PHYAD1") (class "Default")
      (node (ref "IC1") (pin "7") (pinfunction "RXCLK/PHYAD1_7") (pintype "bidirectional"))
      (node (ref "RN1") (pin "1") (pinfunction "1_1") (pintype "passive"))
    )
    (net (code "32") (name "ETH-PHYAD2") (class "Default")
      (node (ref "IC1") (pin "8") (pinfunction "RXD3/PHYAD2_8") (pintype "bidirectional"))
      (node (ref "RN1") (pin "2") (pinfunction "2_2") (pintype "passive"))
    )
    (net (code "33") (name "ETH-RMIISEL") (class "Default")
      (node (ref "IC1") (pin "9") (pinfunction "RXD2/RMIISEL_9") (pintype "bidirectional"))
      (node (ref "RN1") (pin "3") (pinfunction "3_3") (pintype "passive"))
    )
    (net (code "34") (name "ETH-VDDA") (class "Default")
      (node (ref "C3") (pin "1") (pinfunction "1_1") (pintype "passive"))
      (node (ref "C6") (pin "1") (pinfunction "1_1") (pintype "passive"))
      (node (ref "C8") (pin "1") (pinfunction "1_1") (pintype "passive"))
      (node (ref "C9") (pin "1") (pinfunction "1_1") (pintype "passive"))
      (node (ref "IC1") (pin "1") (pinfunction "VDD2A_1") (pintype "power_in"))
      (node (ref "IC1") (pin "27") (pinfunction "VDD1A_27") (pintype "power_in"))
      (node (ref "L1") (pin "2") (pinfunction "2_2") (pintype "passive"))
      (node (ref "POE-ETH") (pin "3") (pinfunction "CR_3") (pintype "passive"))
      (node (ref "POE-ETH") (pin "4") (pinfunction "CT_4") (pintype "passive"))
      (node (ref "R15") (pin "2") (pinfunction "2_2") (pintype "passive"))
      (node (ref "R16") (pin "1") (pinfunction "1_1") (pintype "passive"))
      (node (ref "R17") (pin "2") (pinfunction "2_2") (pintype "passive"))
      (node (ref "R18") (pin "1") (pinfunction "1_1") (pintype "passive"))
      (node (ref "R30") (pin "2") (pinfunction "2_2") (pintype "passive"))
    )
    (net (code "35") (name "ETH-VDDIO") (class "Default")
      (node (ref "C11") (pin "1") (pinfunction "1_1") (pintype "passive"))
      (node (ref "C5") (pin "1") (pinfunction "1_1") (pintype "passive"))
      (node (ref "IC1") (pin "12") (pinfunction "VDDIO_12") (pintype "power_in"))
      (node (ref "L1") (pin "1") (pinfunction "1_1") (pintype "passive"))
      (node (ref "Q4") (pin "3") (pinfunction "D_3") (pintype "passive"))
      (node (ref "R19") (pin "2") (pinfunction "2_2") (pintype "passive"))
      (node (ref "RN1") (pin "6") (pinfunction "6_6") (pintype "passive"))
      (node (ref "RN2") (pin "5") (pinfunction "5_5") (pintype "passive"))
      (node (ref "RN2") (pin "6") (pinfunction "6_6") (pintype "passive"))
      (node (ref "RN2") (pin "7") (pinfunction "7_7") (pintype "passive"))
      (node (ref "RN2") (pin "8") (pinfunction "8_8") (pintype "passive"))
    )
    (net (code "36") (name "GND") (class "Default")
      (node (ref "C1") (pin "2") (pinfunction "2_2") (pintype "passive"))
      (node (ref "C10") (pin "2") (pinfunction "2_2") (pintype "passive"))
      (node (ref "C11") (pin "2") (pinfunction "2_2") (pintype "passive"))
      (node (ref "C12") (pin "2") (pinfunction "2_2") (pintype "passive"))
      (node (ref "C15") (pin "2") (pinfunction "2_2") (pintype "passive"))
      (node (ref "C16") (pin "2") (pinfunction "2_2") (pintype "passive"))
      (node (ref "C2") (pin "2") (pinfunction "2_2") (pintype "passive"))
      (node (ref "C21") (pin "2") (pinfunction "2_2") (pintype "passive"))
      (node (ref "C23") (pin "2") (pinfunction "2_2") (pintype "passive"))
      (node (ref "C24") (pin "2") (pinfunction "2_2") (pintype "passive"))
      (node (ref "C25") (pin "2") (pinfunction "2_2") (pintype "passive"))
      (node (ref "C26") (pin "2") (pinfunction "2_2") (pintype "passive"))
      (node (ref "C27") (pin "2") (pinfunction "2_2") (pintype "passive"))
      (node (ref "C3") (pin "2") (pinfunction "2_2") (pintype "passive"))
      (node (ref "C5") (pin "2") (pinfunction "2_2") (pintype "passive"))
      (node (ref "C6") (pin "2") (pinfunction "2_2") (pintype "passive"))
      (node (ref "C7") (pin "2") (pinfunction "2_2") (pintype "passive"))
      (node (ref "C8") (pin "2") (pinfunction "2_2") (pintype "passive"))
      (node (ref "C9") (pin "2") (pinfunction "2_2") (pintype "passive"))
      (node (ref "D5") (pin "A") (pinfunction "A_A") (pintype "passive"))
      (node (ref "DC1") (pin "5") (pinfunction "-VOUT_5") (pintype "passive"))
      (node (ref "ESP1") (pin "1") (pinfunction "GND_1") (pintype "power_in"))
      (node (ref "ESP1") (pin "15") (pinfunction "GND_15") (pintype "power_in"))
      (node (ref "ESP1") (pin "38") (pinfunction "GND_38") (pintype "power_in"))
      (node (ref "ESP1") (pin "EP1") (pinfunction "EP_EP1") (pintype "passive"))
      (node (ref "ESP1") (pin "EP2") (pinfunction "EP_EP2") (pintype "passive"))
      (node (ref "ESP1") (pin "EP3") (pinfunction "EP_EP3") (pintype "passive"))
      (node (ref "ESP1") (pin "EP4") (pinfunction "EP_EP4") (pintype "passive"))
      (node (ref "ESP1") (pin "EP5") (pinfunction "EP_EP5") (pintype "passive"))
      (node (ref "ESP1") (pin "EP6") (pinfunction "EP_EP6") (pintype "passive"))
      (node (ref "ESP1") (pin "EP7") (pinfunction "EP_EP7") (pintype "passive"))
      (node (ref "ESP1") (pin "EP8") (pinfunction "EP_EP8") (pintype "passive"))
      (node (ref "ESP1") (pin "EP9") (pinfunction "EP_EP9") (pintype "passive"))
      (node (ref "IC1") (pin "24") (pinfunction "TXD2_24") (pintype "input"))
      (node (ref "IC1") (pin "25") (pinfunction "TXD3_25") (pintype "input"))
      (node (ref "IC1") (pin "EP") (pinfunction "GND_EP") (pintype "power_in"))
      (node (ref "IC4") (pin "2") (pinfunction "GND_2") (pintype "power_in"))
      (node (ref "IC6") (pin "3") (pinfunction "GND_3") (pintype "power_in"))
      (node (ref "OK2") (pin "2") (pinfunction "C_2") (pintype "passive"))
      (node (ref "PGD") (pin "C") (pinfunction "C_C") (pintype "passive"))
      (node (ref "Q3") (pin "2") (pinfunction "E_2") (pintype "passive"))
      (node (ref "R11") (pin "2") (pinfunction "2_2") (pintype "passive"))
      (node (ref "R20") (pin "1") (pinfunction "1_1") (pintype "passive"))
      (node (ref "R29") (pin "2") (pinfunction "2_2") (pintype "passive"))
      (node (ref "R35") (pin "2") (pinfunction "2_2") (pintype "passive"))
      (node (ref "R42") (pin "2") (pinfunction "2_2") (pintype "passive"))
      (node (ref "R44") (pin "2") (pinfunction "2_2") (pintype "passive"))
      (node (ref "R47") (pin "2") (pinfunction "2_2") (pintype "passive"))
      (node (ref "R5") (pin "2") (pinfunction "2_2") (pintype "passive"))
      (node (ref "R8") (pin "1") (pinfunction "1_1") (pintype "passive"))
      (node (ref "RN1") (pin "5") (pinfunction "5_5") (pintype "passive"))
      (node (ref "RN1") (pin "7") (pinfunction "7_7") (pintype "passive"))
      (node (ref "RN1") (pin "8") (pinfunction "8_8") (pintype "passive"))
      (node (ref "RST") (pin "3") (pinfunction "2_3") (pintype "passive"))
      (node (ref "RST") (pin "4") (pinfunction "2_4") (pintype "passive"))
      (node (ref "RST") (pin "SH") (pinfunction "M_SH") (pintype "passive"))
      (node (ref "U1") (pin "2") (pinfunction "GND_2") (pintype "power_in"))
      (node (ref "U2") (pin "2") (pinfunction "GND_2") (pintype "power_in"))
      (node (ref "UEXT") (pin "2") (pinfunction "2_2") (pintype "passive"))
      (node (ref "USB") (pin "GND") (pinfunction "GND_GND") (pintype "bidirectional"))
      (node (ref "USB") (pin "MT1") (pinfunction "GND_MT1") (pintype "bidirectional"))
      (node (ref "USB") (pin "MT2") (pinfunction "GND_MT2") (pintype "bidirectional"))
      (node (ref "USB") (pin "MT3") (pinfunction "GND_MT3") (pintype "bidirectional"))
      (node (ref "USB") (pin "MT4") (pinfunction "GND_MT4") (pintype "bidirectional"))
      (node (ref "USB") (pin "MT5") (pinfunction "GND_MT5") (pintype "bidirectional"))
      (node (ref "USB") (pin "MT6") (pinfunction "GND_MT6") (pintype "bidirectional"))
      (node (ref "USD") (pin "6") (pinfunction "GND_6") (pintype "power_in"))
      (node (ref "USD") (pin "S1") (pinfunction "SHIELD_S1") (pintype "passive"))
      (node (ref "USD") (pin "S2") (pinfunction "SHIELD_S2") (pintype "passive"))
      (node (ref "USD") (pin "S3") (pinfunction "SHIELD_S3") (pintype "passive"))
      (node (ref "USD") (pin "S4") (pinfunction "SHIELD_S4") (pintype "passive"))
    )
    (net (code "37") (name "Net-(BSB-Pad1)") (class "Default")
      (node (ref "BSB") (pin "1") (pinfunction "1_1") (pintype "passive"))
      (node (ref "R10") (pin "1") (pinfunction "1_1") (pintype "passive"))
    )
    (net (code "38") (name "Net-(BSBB-1)") (class "Default")
      (node (ref "BSB") (pin "2") (pinfunction "1_2") (pintype "passive"))
      (node (ref "R9") (pin "1") (pinfunction "1_1") (pintype "passive"))
    )
    (net (code "39") (name "Net-(C2-Pad1)") (class "Default")
      (node (ref "C2") (pin "1") (pinfunction "1_1") (pintype "passive"))
      (node (ref "POE-ETH") (pin "SH1") (pinfunction "SLD_SH1") (pintype "passive"))
      (node (ref "POE-ETH") (pin "SH2") (pinfunction "SLD_SH2") (pintype "passive"))
    )
    (net (code "40") (name "Net-(C17-Pad1)") (class "Default")
      (node (ref "C17") (pin "1") (pinfunction "1_1") (pintype "passive"))
      (node (ref "R39") (pin "2") (pinfunction "2_2") (pintype "passive"))
    )
    (net (code "41") (name "Net-(D2-PadC)") (class "Default")
      (node (ref "D2") (pin "C") (pinfunction "C_C") (pintype "passive"))
      (node (ref "D3") (pin "1") (pinfunction "1_1") (pintype "passive"))
      (node (ref "R9") (pin "2") (pinfunction "2_2") (pintype "passive"))
    )
    (net (code "42") (name "Net-(IC1-NRST)") (class "Default")
      (node (ref "C12") (pin "1") (pinfunction "1_1") (pintype "passive"))
      (node (ref "IC1") (pin "19") (pinfunction "NRST_19") (pintype "input"))
      (node (ref "R19") (pin "1") (pinfunction "1_1") (pintype "passive"))
    )
    (net (code "43") (name "Net-(IC1-RBIAS)") (class "Default")
      (node (ref "IC1") (pin "32") (pinfunction "RBIAS_32") (pintype "passive"))
      (node (ref "R20") (pin "2") (pinfunction "2_2") (pintype "passive"))
    )
    (net (code "44") (name "Net-(IC1-RXN)") (class "Default")
      (node (ref "IC1") (pin "30") (pinfunction "RXN_30") (pintype "bidirectional"))
      (node (ref "POE-ETH") (pin "2") (pinfunction "RD-_2") (pintype "passive"))
      (node (ref "R17") (pin "1") (pinfunction "1_1") (pintype "passive"))
      (node (ref "U1") (pin "3") (pinfunction "IO2_3") (pintype "passive"))
    )
    (net (code "45") (name "Net-(IC1-RXP)") (class "Default")
      (node (ref "IC1") (pin "31") (pinfunction "RXP_31") (pintype "bidirectional"))
      (node (ref "POE-ETH") (pin "1") (pinfunction "RD+_1") (pintype "passive"))
      (node (ref "R18") (pin "2") (pinfunction "2_2") (pintype "passive"))
      (node (ref "U1") (pin "4") (pinfunction "IO3_4") (pintype "passive"))
    )
    (net (code "46") (name "Net-(IC1-TXN)") (class "Default")
      (node (ref "IC1") (pin "28") (pinfunction "TXN_28") (pintype "bidirectional"))
      (node (ref "POE-ETH") (pin "6") (pinfunction "TD-_6") (pintype "passive"))
      (node (ref "R15") (pin "1") (pinfunction "1_1") (pintype "passive"))
      (node (ref "U1") (pin "5") (pinfunction "IO4_5") (pintype "passive"))
    )
    (net (code "47") (name "Net-(IC1-TXP)") (class "Default")
      (node (ref "IC1") (pin "29") (pinfunction "TXP_29") (pintype "bidirectional"))
      (node (ref "POE-ETH") (pin "5") (pinfunction "TD+_5") (pintype "passive"))
      (node (ref "R16") (pin "2") (pinfunction "2_2") (pintype "passive"))
      (node (ref "U1") (pin "1") (pinfunction "IO1_1") (pintype "passive"))
    )
    (net (code "48") (name "Net-(IC1-VDDCR)") (class "Default")
      (node (ref "C10") (pin "1") (pinfunction "1_1") (pintype "passive"))
      (node (ref "C7") (pin "1") (pinfunction "1_1") (pintype "passive"))
      (node (ref "IC1") (pin "6") (pinfunction "VDDCR_6") (pintype "power_in"))
    )
    (net (code "49") (name "Net-(IC2-CLASS)") (class "Default")
      (node (ref "IC2") (pin "2") (pinfunction "CLASS_2") (pintype "input"))
      (node (ref "R27") (pin "1") (pinfunction "1_1") (pintype "passive"))
    )
    (net (code "50") (name "Net-(IC2-DET)") (class "Default")
      (node (ref "IC2") (pin "3") (pinfunction "DET_3") (pintype "input"))
      (node (ref "R25") (pin "2") (pinfunction "2_2") (pintype "passive"))
    )
    (net (code "51") (name "Net-(IC2-ILIM)") (class "Default")
      (node (ref "IC2") (pin "1") (pinfunction "ILIM_1") (pintype "input"))
      (node (ref "R26") (pin "1") (pinfunction "1_1") (pintype "passive"))
    )
    (net (code "52") (name "Net-(IC2-UVLO)") (class "Default")
      (node (ref "IC2") (pin "7") (pinfunction "UVLO_7") (pintype "input"))
      (node (ref "R23") (pin "1") (pinfunction "1_1") (pintype "passive"))
      (node (ref "R24") (pin "2") (pinfunction "2_2") (pintype "passive"))
    )
    (net (code "53") (name "Net-(IC3-BS)") (class "Default")
      (node (ref "IC3") (pin "8") (pinfunction "BS_8") (pintype "power_in"))
      (node (ref "R39") (pin "1") (pinfunction "1_1") (pintype "passive"))
    )
    (net (code "54") (name "Net-(IC3-FB)") (class "Default")
      (node (ref "C19") (pin "2") (pinfunction "2_2") (pintype "passive"))
      (node (ref "IC3") (pin "5") (pinfunction "FB_5") (pintype "input"))
      (node (ref "R36") (pin "1") (pinfunction "1_1") (pintype "passive"))
      (node (ref "R37") (pin "1") (pinfunction "1_1") (pintype "passive"))
    )
    (net (code "55") (name "Net-(IC3-ILIM-Pad2)") (class "Default")
      (node (ref "IC3") (pin "2") (pinfunction "ILIM_2") (pintype "power_in"))
      (node (ref "IC3") (pin "EP") (pinfunction "ILIM_EP") (pintype "power_in"))
      (node (ref "R21") (pin "2") (pinfunction "2_2") (pintype "passive"))
    )
    (net (code "56") (name "Net-(IC3-SW)") (class "Default")
      (node (ref "C17") (pin "2") (pinfunction "2_2") (pintype "passive"))
      (node (ref "D1") (pin "C") (pinfunction "C_C") (pintype "passive"))
      (node (ref "IC3") (pin "1") (pinfunction "SW_1") (pintype "output"))
      (node (ref "L3") (pin "1") (pinfunction "1_1") (pintype "passive"))
    )
    (net (code "57") (name "Net-(IC4-FB)") (class "Default")
      (node (ref "IC4") (pin "5") (pinfunction "FB_5") (pintype "input"))
      (node (ref "R40") (pin "1") (pinfunction "1_1") (pintype "passive"))
      (node (ref "R41") (pin "2") (pinfunction "2_2") (pintype "passive"))
    )
    (net (code "58") (name "Net-(IC4-LX)") (class "Default")
      (node (ref "IC4") (pin "3") (pinfunction "LX_3") (pintype "output"))
      (node (ref "L4") (pin "1") (pinfunction "1_1") (pintype "passive"))
    )
    (net (code "59") (name "Net-(IC6-TNOW{slash}~{DTR})") (class "Default")
      (node (ref "IC6") (pin "6") (pinfunction "TNOW/~{DTR}_6") (pintype "bidirectional"))
      (node (ref "Q5") (pin "2") (pinfunction "E_2") (pintype "passive"))
      (node (ref "R46") (pin "2") (pinfunction "2_2") (pintype "passive"))
      (node (ref "R50") (pin "1") (pinfunction "1_1") (pintype "passive"))
    )
    (net (code "60") (name "Net-(IC6-TXD)") (class "Default")
      (node (ref "IC6") (pin "8") (pinfunction "TXD_8") (pintype "output"))
      (node (ref "R49") (pin "1") (pinfunction "1_1") (pintype "passive"))
    )
    (net (code "61") (name "Net-(IC6-~{CTS})") (class "Default")
      (node (ref "IC6") (pin "5") (pinfunction "~{CTS}_5") (pintype "input"))
      (node (ref "R50") (pin "2") (pinfunction "2_2") (pintype "passive"))
    )
    (net (code "62") (name "Net-(IC6-~{RTS})") (class "Default")
      (node (ref "IC6") (pin "4") (pinfunction "~{RTS}_4") (pintype "output"))
      (node (ref "Q6") (pin "2") (pinfunction "E_2") (pintype "passive"))
      (node (ref "R45") (pin "2") (pinfunction "2_2") (pintype "passive"))
    )
    (net (code "63") (name "Net-(OK1-A)") (class "Default")
      (node (ref "OK1") (pin "1") (pinfunction "A_1") (pintype "passive"))
      (node (ref "R2") (pin "2") (pinfunction "2_2") (pintype "passive"))
    )
    (net (code "64") (name "Net-(OK1-BAS)") (class "Default")
      (node (ref "OK1") (pin "6") (pinfunction "BAS_6") (pintype "passive"))
      (node (ref "R4") (pin "2") (pinfunction "2_2") (pintype "passive"))
    )
    (net (code "65") (name "Net-(OK1-C)") (class "Default")
      (node (ref "ACT") (pin "A") (pinfunction "A_A") (pintype "passive"))
      (node (ref "OK1") (pin "2") (pinfunction "C_2") (pintype "passive"))
    )
    (net (code "66") (name "Net-(OK2-A)") (class "Default")
      (node (ref "OK2") (pin "1") (pinfunction "A_1") (pintype "passive"))
      (node (ref "R3") (pin "2") (pinfunction "2_2") (pintype "passive"))
    )
    (net (code "67") (name "Net-(OK2-BAS)") (class "Default")
      (node (ref "OK2") (pin "6") (pinfunction "BAS_6") (pintype "passive"))
      (node (ref "R1") (pin "2") (pinfunction "2_2") (pintype "passive"))
    )
    (net (code "68") (name "Net-(OK2-EMI)") (class "Default")
      (node (ref "OK2") (pin "4") (pinfunction "EMI_4") (pintype "passive"))
      (node (ref "Q1") (pin "1") (pinfunction "B_1") (pintype "passive"))
      (node (ref "R1") (pin "1") (pinfunction "1_1") (pintype "passive"))
      (node (ref "R7") (pin "2") (pinfunction "2_2") (pintype "passive"))
    )
    (net (code "69") (name "Net-(OPT-Pad2)") (class "Default")
      (node (ref "OPT") (pin "2") (pinfunction "2_2") (pintype "passive"))
      (node (ref "R35") (pin "1") (pinfunction "1_1") (pintype "passive"))
    )
    (net (code "70") (name "Net-(PGD-PadA)") (class "Default")
      (node (ref "PGD") (pin "A") (pinfunction "A_A") (pintype "passive"))
      (node (ref "R48") (pin "1") (pinfunction "1_1") (pintype "passive"))
    )
    (net (code "71") (name "Net-(POE-ETH-GA)") (class "Default")
      (node (ref "POE-ETH") (pin "13") (pinfunction "GA_13") (pintype "passive"))
      (node (ref "R30") (pin "1") (pinfunction "1_1") (pintype "passive"))
    )
    (net (code "72") (name "Net-(POE-ETH-YK)") (class "Default")
      (node (ref "POE-ETH") (pin "12") (pinfunction "YK_12") (pintype "passive"))
      (node (ref "R29") (pin "1") (pinfunction "1_1") (pintype "passive"))
    )
    (net (code "73") (name "Net-(Q2-PadB)") (class "Default")
      (node (ref "Q2") (pin "B") (pinfunction "B_B") (pintype "passive"))
      (node (ref "R6") (pin "1") (pinfunction "1_1") (pintype "passive"))
    )
    (net (code "74") (name "Net-(Q2-PadC)") (class "Default")
      (node (ref "Q2") (pin "C") (pinfunction "C_C") (pintype "passive"))
      (node (ref "R3") (pin "1") (pinfunction "1_1") (pintype "passive"))
    )
    (net (code "75") (name "Net-(Q3-B)") (class "Default")
      (node (ref "Q3") (pin "1") (pinfunction "B_1") (pintype "passive"))
      (node (ref "R11") (pin "1") (pinfunction "1_1") (pintype "passive"))
      (node (ref "R14") (pin "2") (pinfunction "2_2") (pintype "passive"))
    )
    (net (code "76") (name "Net-(Q3-C)") (class "Default")
      (node (ref "Q3") (pin "3") (pinfunction "C_3") (pintype "passive"))
      (node (ref "R12") (pin "1") (pinfunction "1_1") (pintype "passive"))
    )
    (net (code "77") (name "Net-(Q4-G)") (class "Default")
      (node (ref "C4") (pin "2") (pinfunction "2_2") (pintype "passive"))
      (node (ref "Q4") (pin "1") (pinfunction "G_1") (pintype "passive"))
      (node (ref "R12") (pin "2") (pinfunction "2_2") (pintype "passive"))
      (node (ref "R13") (pin "1") (pinfunction "1_1") (pintype "passive"))
    )
    (net (code "78") (name "Net-(Q5-B)") (class "Default")
      (node (ref "Q5") (pin "1") (pinfunction "B_1") (pintype "passive"))
      (node (ref "R45") (pin "1") (pinfunction "1_1") (pintype "passive"))
    )
    (net (code "79") (name "Net-(Q6-B)") (class "Default")
      (node (ref "Q6") (pin "1") (pinfunction "B_1") (pintype "passive"))
      (node (ref "R46") (pin "1") (pinfunction "1_1") (pintype "passive"))
    )
    (net (code "80") (name "Net-(R36-Pad2)") (class "Default")
      (node (ref "R36") (pin "2") (pinfunction "2_2") (pintype "passive"))
      (node (ref "R38") (pin "2") (pinfunction "2_2") (pintype "passive"))
    )
    (net (code "81") (name "Net-(R41-Pad1)") (class "Default")
      (node (ref "R41") (pin "1") (pinfunction "1_1") (pintype "passive"))
      (node (ref "R42") (pin "1") (pinfunction "1_1") (pintype "passive"))
    )
    (net (code "82") (name "Net-(USD-CS{slash}DAT3)") (class "Default")
      (node (ref "RN3") (pin "1") (pinfunction "1_1") (pintype "passive"))
      (node (ref "USD") (pin "2") (pinfunction "CS/DAT3_2") (pintype "bidirectional"))
    )
    (net (code "83") (name "Net-(USD-DAT0)") (class "Default")
      (node (ref "R31") (pin "2") (pinfunction "2_2") (pintype "passive"))
      (node (ref "USD") (pin "7") (pinfunction "DAT0_7") (pintype "bidirectional"))
    )
    (net (code "84") (name "Net-(USD-DAT1)") (class "Default")
      (node (ref "RN3") (pin "3") (pinfunction "3_3") (pintype "passive"))
      (node (ref "USD") (pin "8") (pinfunction "DAT1_8") (pintype "bidirectional"))
    )
    (net (code "85") (name "Net-(USD-DAT2)") (class "Default")
      (node (ref "RN3") (pin "2") (pinfunction "2_2") (pintype "passive"))
      (node (ref "USD") (pin "1") (pinfunction "DAT2_1") (pintype "bidirectional"))
    )
    (net (code "86") (name "Net-(USD-SCLK)") (class "Default")
      (node (ref "R33") (pin "2") (pinfunction "2_2") (pintype "passive"))
      (node (ref "USD") (pin "5") (pinfunction "SCLK_5") (pintype "bidirectional"))
    )
    (net (code "87") (name "PHY-PWR") (class "Default")
      (node (ref "ESP1") (pin "14") (pinfunction "GPIO12_14") (pintype "bidirectional"))
      (node (ref "R14") (pin "1") (pinfunction "1_1") (pintype "passive"))
    )
    (net (code "88") (name "POE-5V0") (class "Default")
      (node (ref "C18") (pin "+") (pinfunction "+_+") (pintype "passive"))
      (node (ref "C19") (pin "1") (pinfunction "1_1") (pintype "passive"))
      (node (ref "C20") (pin "1") (pinfunction "1_1") (pintype "passive"))
      (node (ref "C22") (pin "1") (pinfunction "1_1") (pintype "passive"))
      (node (ref "DC1") (pin "1") (pinfunction "+VIN_1") (pintype "passive"))
      (node (ref "L3") (pin "2") (pinfunction "2_2") (pintype "passive"))
      (node (ref "R38") (pin "1") (pinfunction "1_1") (pintype "passive"))
    )
    (net (code "89") (name "POE-GND") (class "Default")
      (node (ref "C14") (pin "-") (pinfunction "-_-") (pintype "passive"))
      (node (ref "C18") (pin "-") (pinfunction "-_-") (pintype "passive"))
      (node (ref "C21") (pin "1") (pinfunction "1_1") (pintype "passive"))
      (node (ref "C22") (pin "2") (pinfunction "2_2") (pintype "passive"))
      (node (ref "D1") (pin "A") (pinfunction "A_A") (pintype "passive"))
      (node (ref "DC1") (pin "2") (pinfunction "-VIN_2") (pintype "passive"))
      (node (ref "IC2") (pin "5") (pinfunction "RTN_5") (pintype "power_in"))
      (node (ref "IC3") (pin "4") (pinfunction "GND_4") (pintype "power_in"))
      (node (ref "R22") (pin "2") (pinfunction "2_2") (pintype "passive"))
      (node (ref "R37") (pin "2") (pinfunction "2_2") (pintype "passive"))
    )
    (net (code "90") (name "POE-PG") (class "Default")
      (node (ref "IC2") (pin "6") (pinfunction "PG_6") (pintype "output"))
      (node (ref "IC3") (pin "6") (pinfunction "EN_6") (pintype "input"))
    )
    (net (code "91") (name "POE-V+") (class "Default")
      (node (ref "C13") (pin "1") (pinfunction "1_1") (pintype "passive"))
      (node (ref "C14") (pin "+") (pinfunction "+_+") (pintype "passive"))
      (node (ref "D4") (pin "C") (pinfunction "C_C") (pintype "passive"))
      (node (ref "IC2") (pin "8") (pinfunction "VDD_8") (pintype "power_in"))
      (node (ref "IC3") (pin "3") (pinfunction "VIN_3") (pintype "power_in"))
      (node (ref "POE-ETH") (pin "9") (pinfunction "V+_9") (pintype "output"))
      (node (ref "R21") (pin "1") (pinfunction "1_1") (pintype "passive"))
      (node (ref "R22") (pin "1") (pinfunction "1_1") (pintype "passive"))
      (node (ref "R24") (pin "1") (pinfunction "1_1") (pintype "passive"))
      (node (ref "R25") (pin "1") (pinfunction "1_1") (pintype "passive"))
    )
    (net (code "92") (name "POE-V-") (class "Default")
      (node (ref "C13") (pin "2") (pinfunction "2_2") (pintype "passive"))
      (node (ref "D4") (pin "A") (pinfunction "A_A") (pintype "passive"))
      (node (ref "IC2") (pin "4") (pinfunction "VSS_4") (pintype "power_in"))
      (node (ref "POE-ETH") (pin "10") (pinfunction "V-_10") (pintype "output"))
      (node (ref "R23") (pin "2") (pinfunction "2_2") (pintype "passive"))
      (node (ref "R26") (pin "2") (pinfunction "2_2") (pintype "passive"))
      (node (ref "R27") (pin "2") (pinfunction "2_2") (pintype "passive"))
    )
    (net (code "93") (name "PWR-SNS") (class "Default")
      (node (ref "C27") (pin "1") (pinfunction "1_1") (pintype "passive"))
      (node (ref "ESP1") (pin "5") (pinfunction "SENSOR_VN_5") (pintype "bidirectional"))
      (node (ref "R43") (pin "2") (pinfunction "2_2") (pintype "passive"))
      (node (ref "R44") (pin "1") (pinfunction "1_1") (pintype "passive"))
    )
    (net (code "94") (name "SD-VCC") (class "Default")
      (node (ref "C15") (pin "1") (pinfunction "1_1") (pintype "passive"))
      (node (ref "C16") (pin "1") (pinfunction "1_1") (pintype "passive"))
      (node (ref "L2") (pin "2") (pinfunction "2_2") (pintype "passive"))
      (node (ref "USD") (pin "4") (pinfunction "VCC_4") (pintype "power_in"))
    )
    (net (code "95") (name "UEXT-RX") (class "Default")
      (node (ref "ESP1") (pin "8") (pinfunction "GPIO32_8") (pintype "bidirectional"))
      (node (ref "RN4") (pin "1") (pinfunction "1_1") (pintype "passive"))
      (node (ref "UEXT") (pin "4") (pinfunction "4_4") (pintype "passive"))
    )
    (net (code "96") (name "UEXT-TX") (class "Default")
      (node (ref "ESP1") (pin "9") (pinfunction "GPIO33_9") (pintype "bidirectional"))
      (node (ref "UEXT") (pin "3") (pinfunction "3_3") (pintype "passive"))
    )
    (net (code "97") (name "USB-D+") (class "Default")
      (node (ref "IC6") (pin "1") (pinfunction "D+_1") (pintype "bidirectional"))
      (node (ref "U2") (pin "5") (pinfunction "IO4_5") (pintype "passive"))
      (node (ref "USB") (pin "D+") (pinfunction "D+_D+") (pintype "bidirectional"))
    )
    (net (code "98") (name "USB-D-") (class "Default")
      (node (ref "IC6") (pin "2") (pinfunction "D-_2") (pintype "bidirectional"))
      (node (ref "U2") (pin "4") (pinfunction "IO3_4") (pintype "passive"))
      (node (ref "USB") (pin "D-") (pinfunction "D-_D-") (pintype "bidirectional"))
    )
    (net (code "99") (name "USB-VBUS") (class "Default")
      (node (ref "Q7") (pin "3") (pinfunction "D_3") (pintype "passive"))
      (node (ref "USB") (pin "VBUS") (pinfunction "VCC_VBUS") (pintype "bidirectional"))
    )
    (net (code "100") (name "unconnected-(ESP1-GPIO35-Pad7)") (class "Default")
      (node (ref "ESP1") (pin "7") (pinfunction "GPIO35_7") (pintype "bidirectional"))
    )
    (net (code "101") (name "unconnected-(IC1-CRS-Pad14)") (class "Default")
      (node (ref "IC1") (pin "14") (pinfunction "CRS_14") (pintype "bidirectional"))
    )
    (net (code "102") (name "unconnected-(IC1-RXDV-Pad26)") (class "Default")
      (node (ref "IC1") (pin "26") (pinfunction "RXDV_26") (pintype "bidirectional"))
    )
    (net (code "103") (name "unconnected-(IC1-TXCLK-Pad20)") (class "Default")
      (node (ref "IC1") (pin "20") (pinfunction "TXCLK_20") (pintype "bidirectional"))
    )
    (net (code "104") (name "unconnected-(IC1-TXER{slash}TXD4-Pad18)") (class "Default")
      (node (ref "IC1") (pin "18") (pinfunction "TXER/TXD4_18") (pintype "bidirectional"))
    )
    (net (code "105") (name "unconnected-(IC1-XTAL2-Pad4)") (class "Default")
      (node (ref "IC1") (pin "4") (pinfunction "XTAL2_4") (pintype "output"))
    )
    (net (code "106") (name "unconnected-(IC3-POK-Pad7)") (class "Default")
      (node (ref "IC3") (pin "7") (pinfunction "POK_7") (pintype "output"))
    )
    (net (code "107") (name "unconnected-(USB-PadID)") (class "Default")
      (node (ref "USB") (pin "ID") (pinfunction "ID_ID") (pintype "bidirectional"))
    )
    (net (code "108") (name "unconnected-(USD-CDET-Pad9)") (class "Default")
      (node (ref "USD") (pin "9") (pinfunction "CDET_9") (pintype "passive"))
    )
  )
)
